# FindMeSAT_MB_1V0.net
KiCad netlist of a schematic drawn in EAGLE
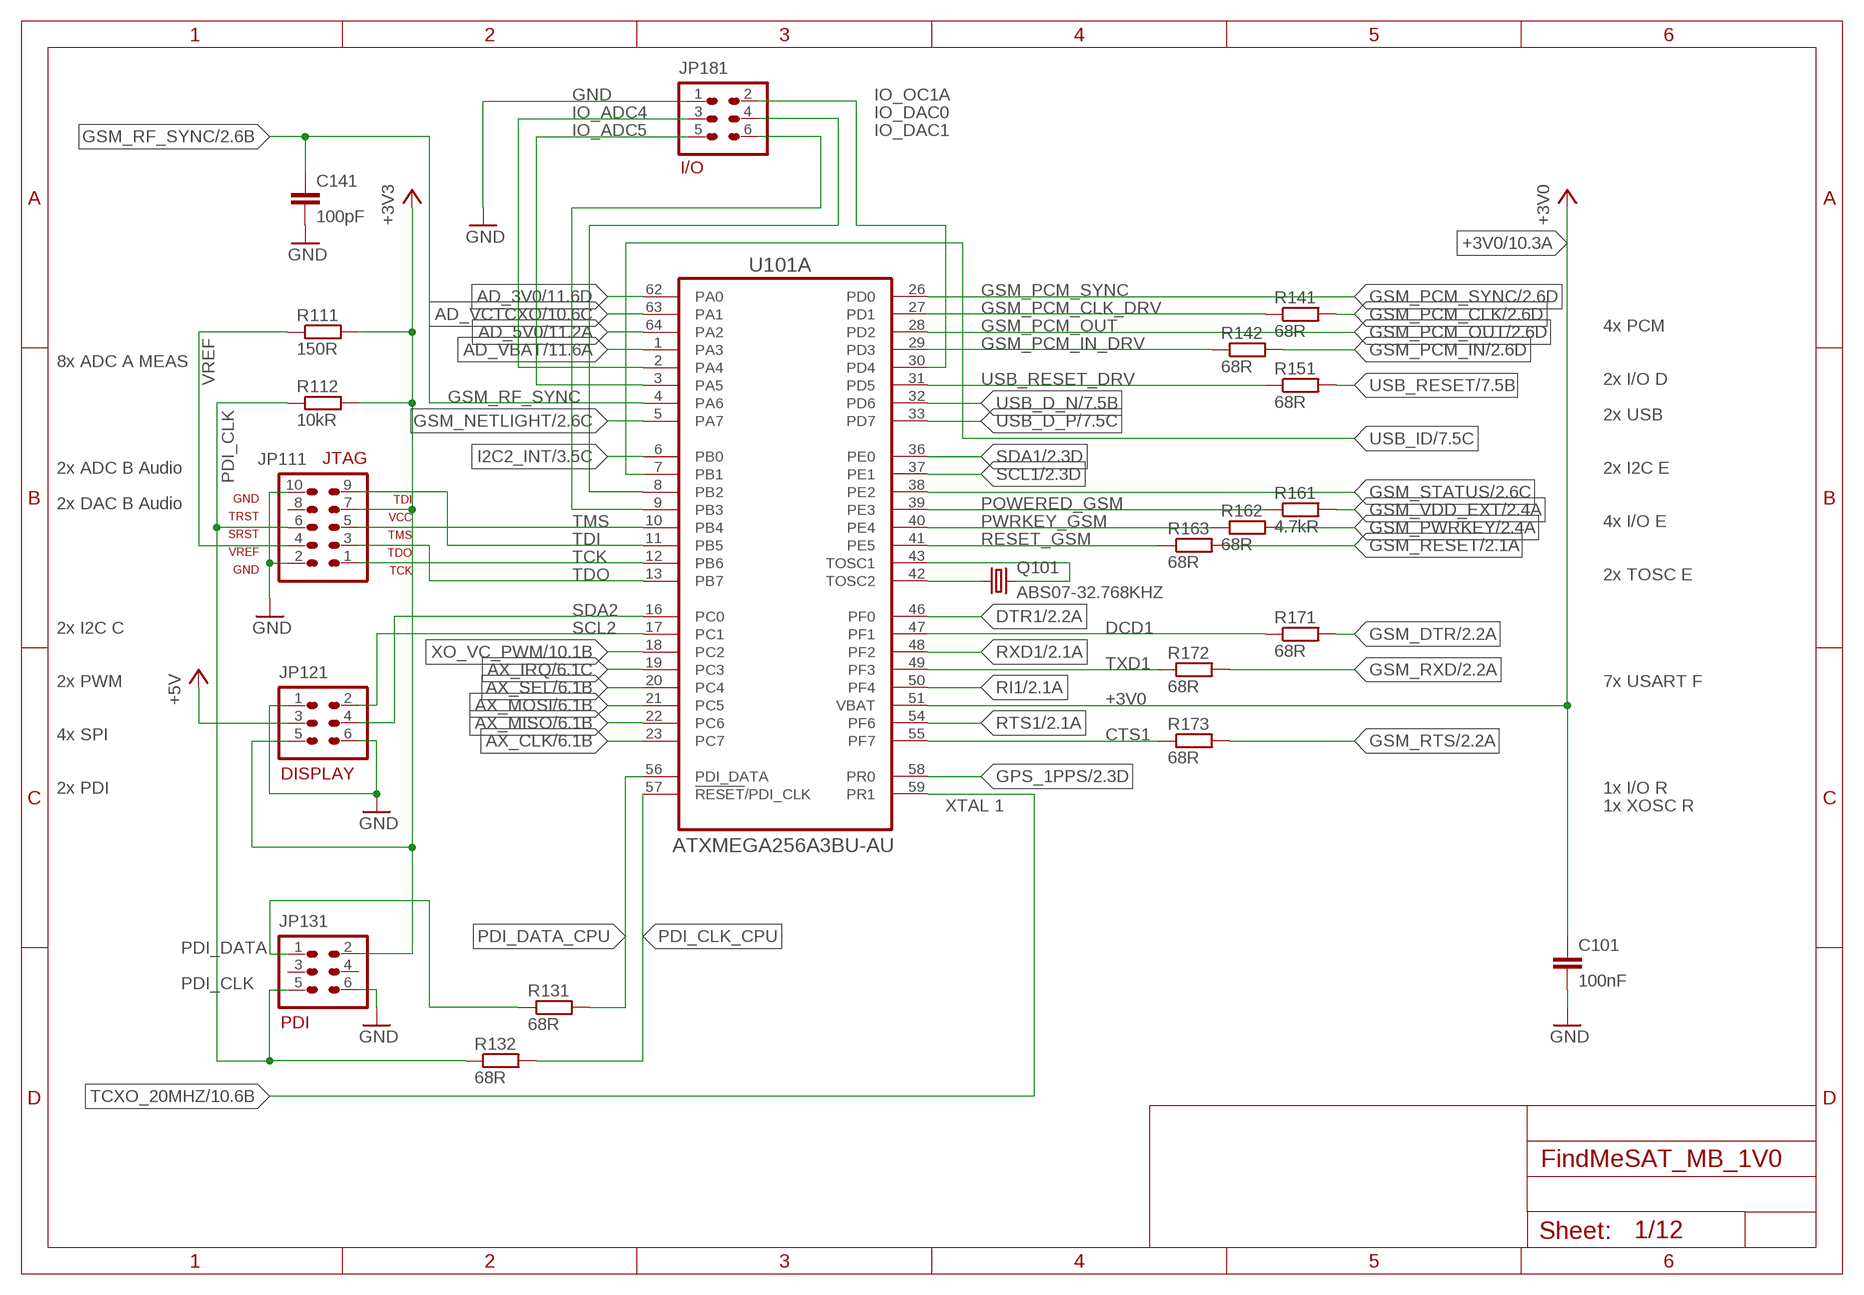
[diagram p0: schematic, sheet 1]
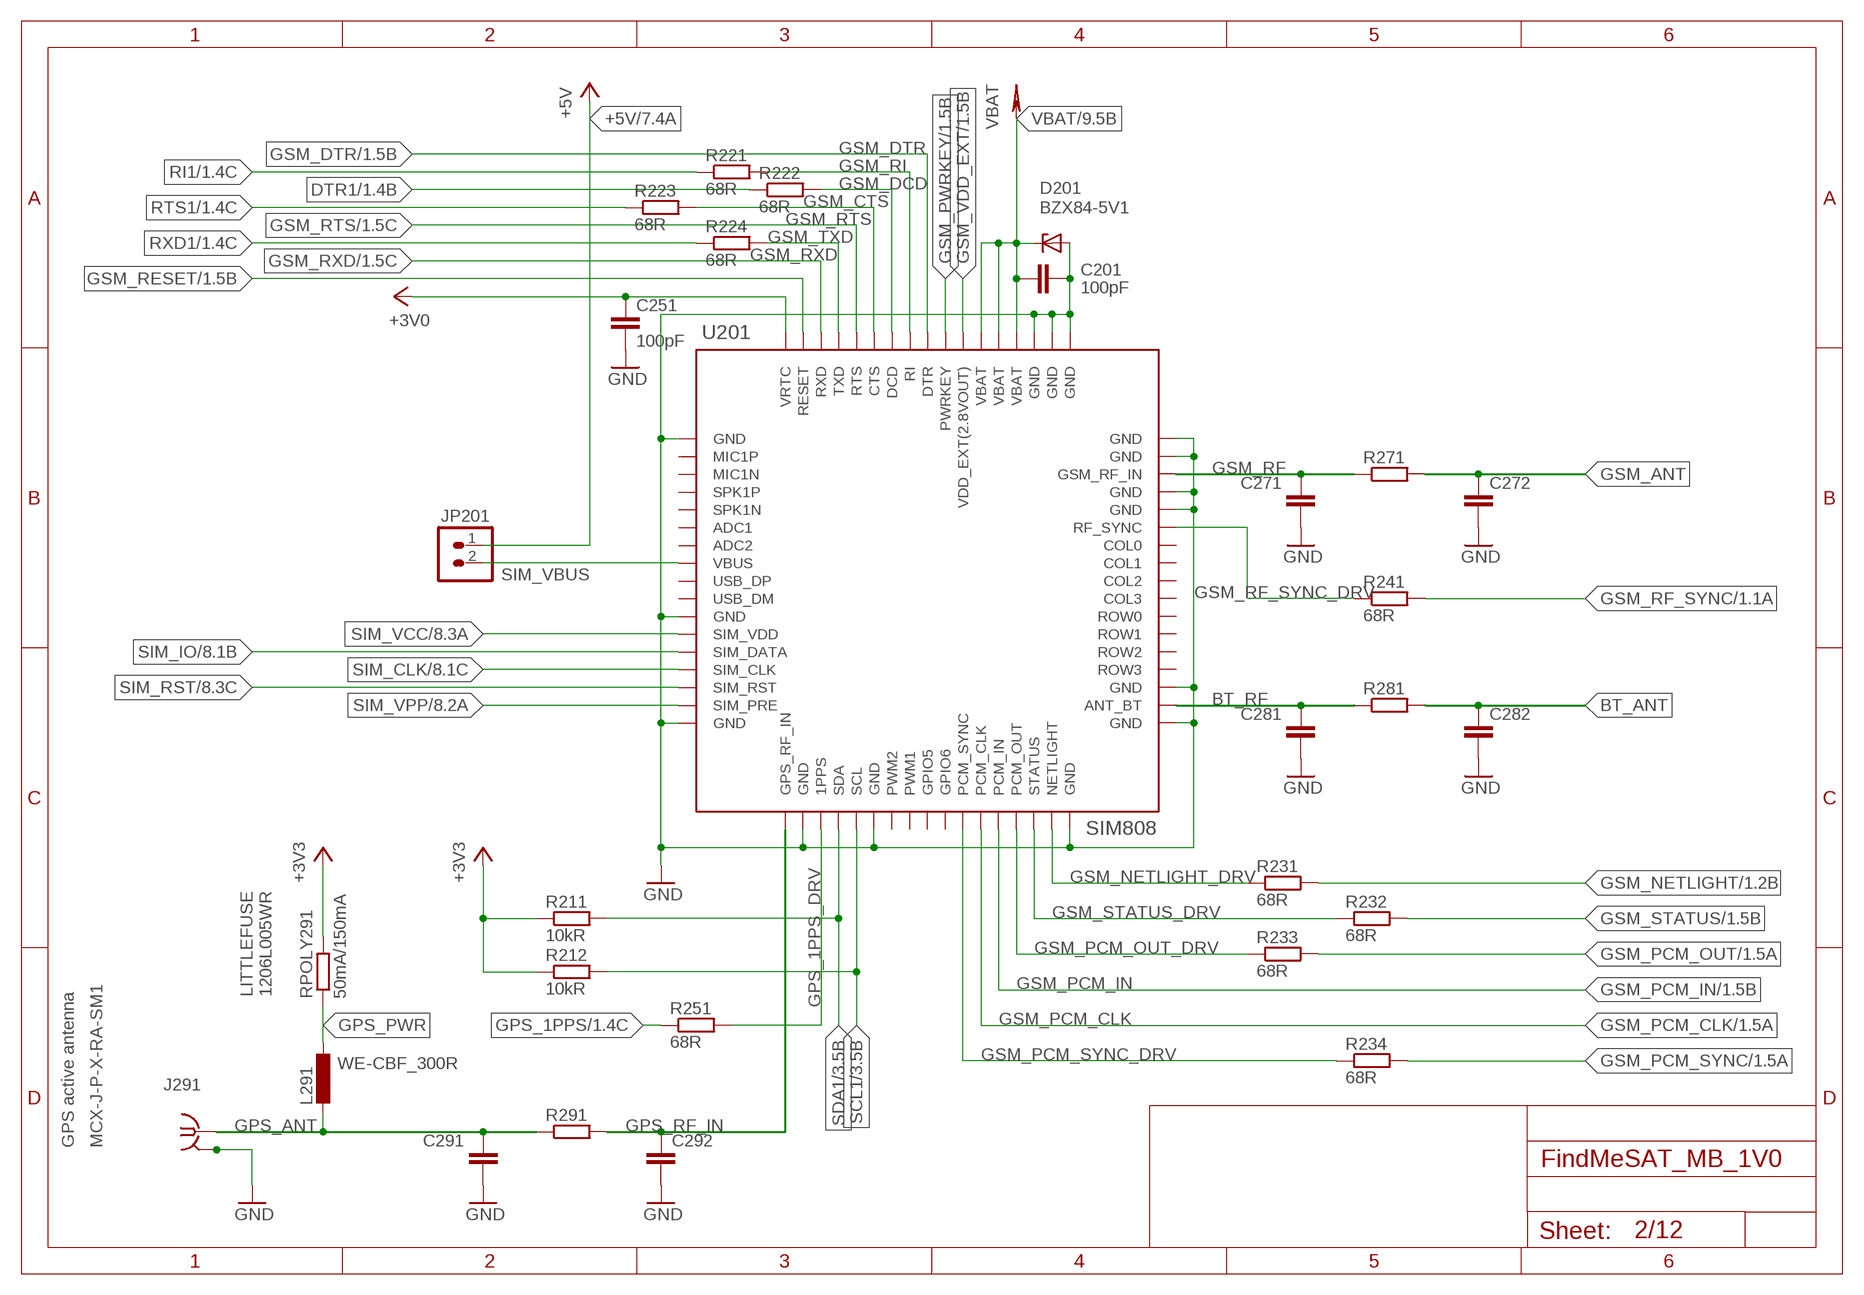
[diagram p1: schematic, sheet 2]
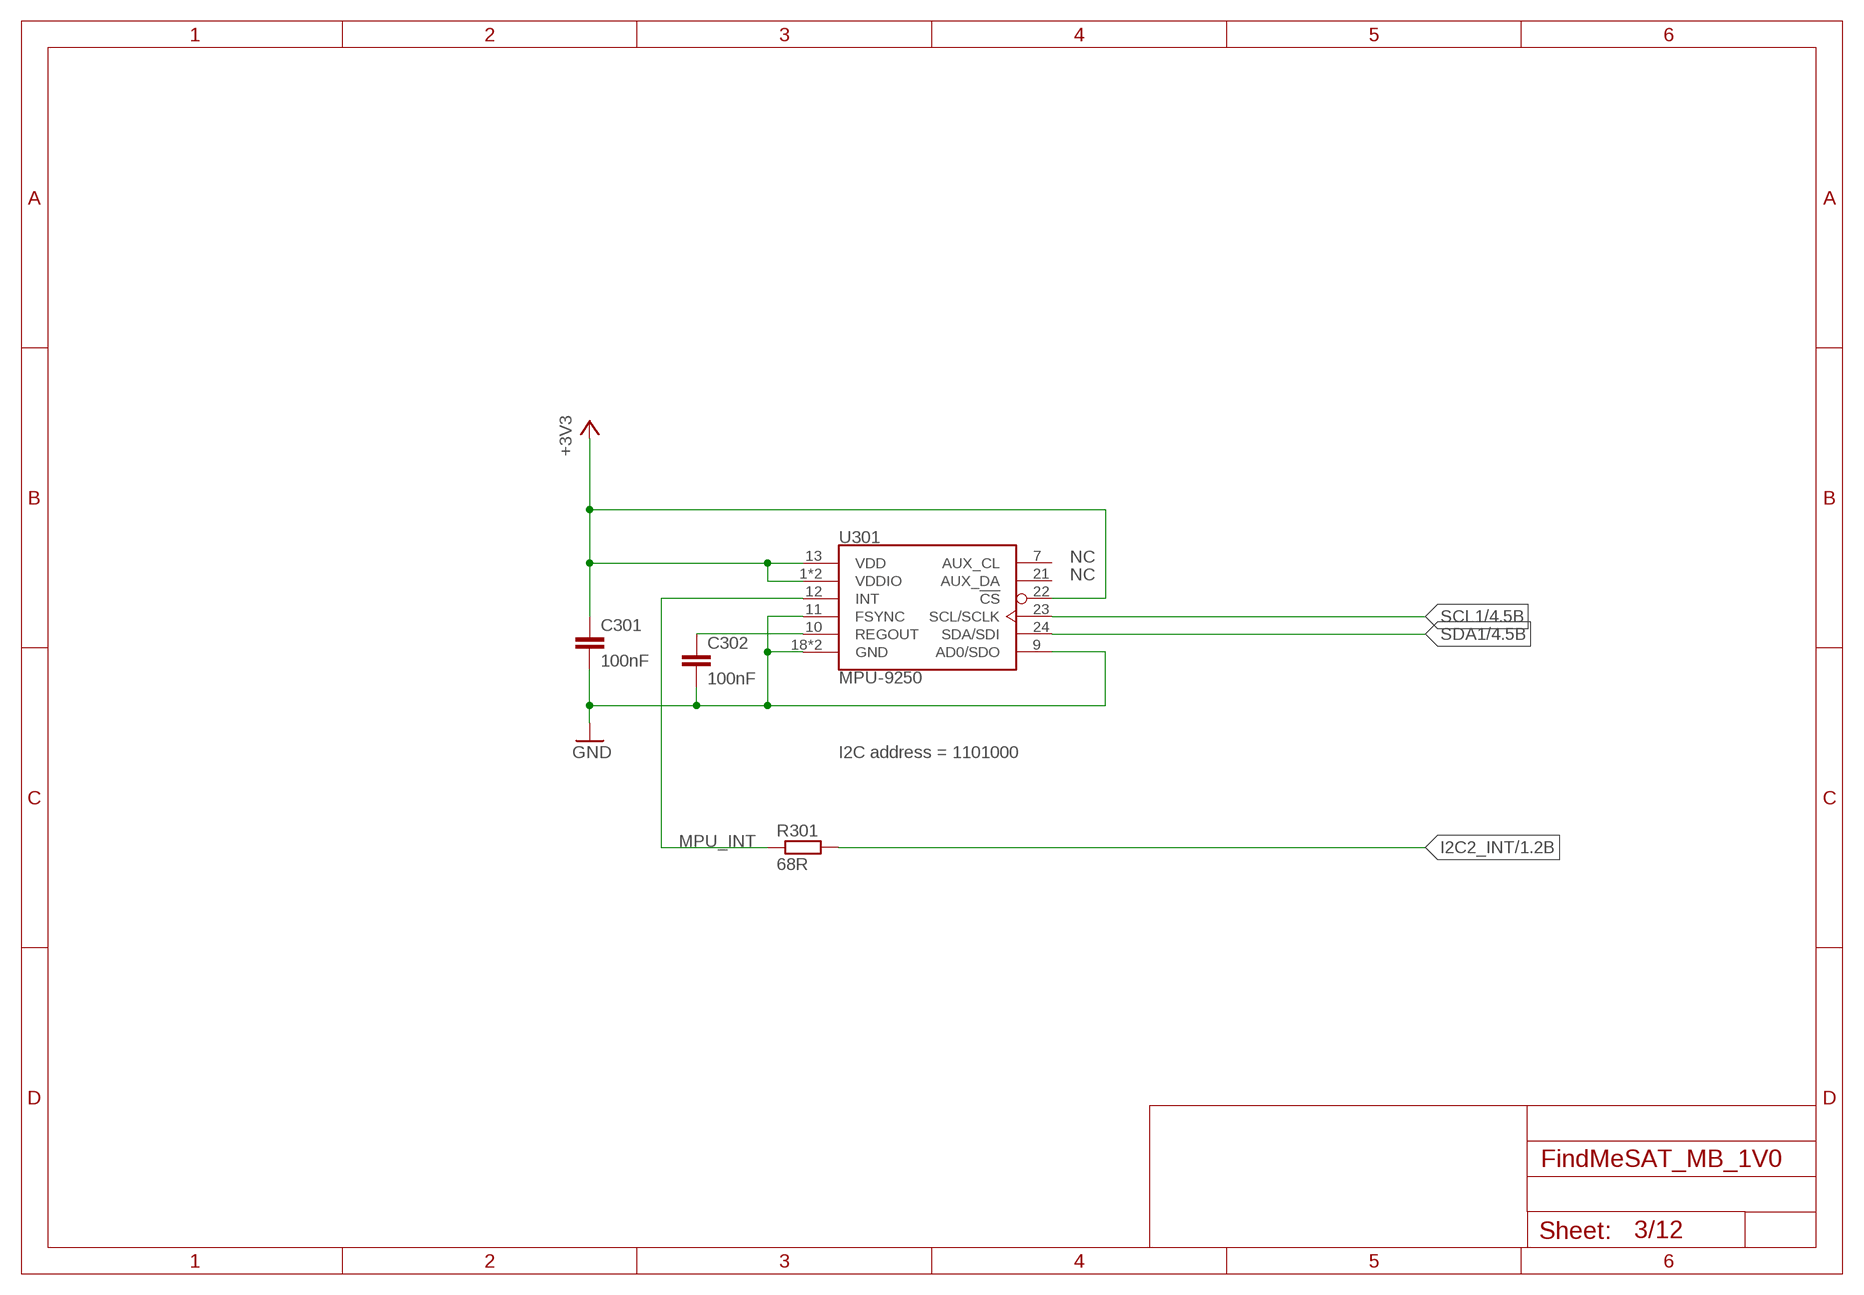
[diagram p2: schematic, sheet 3]
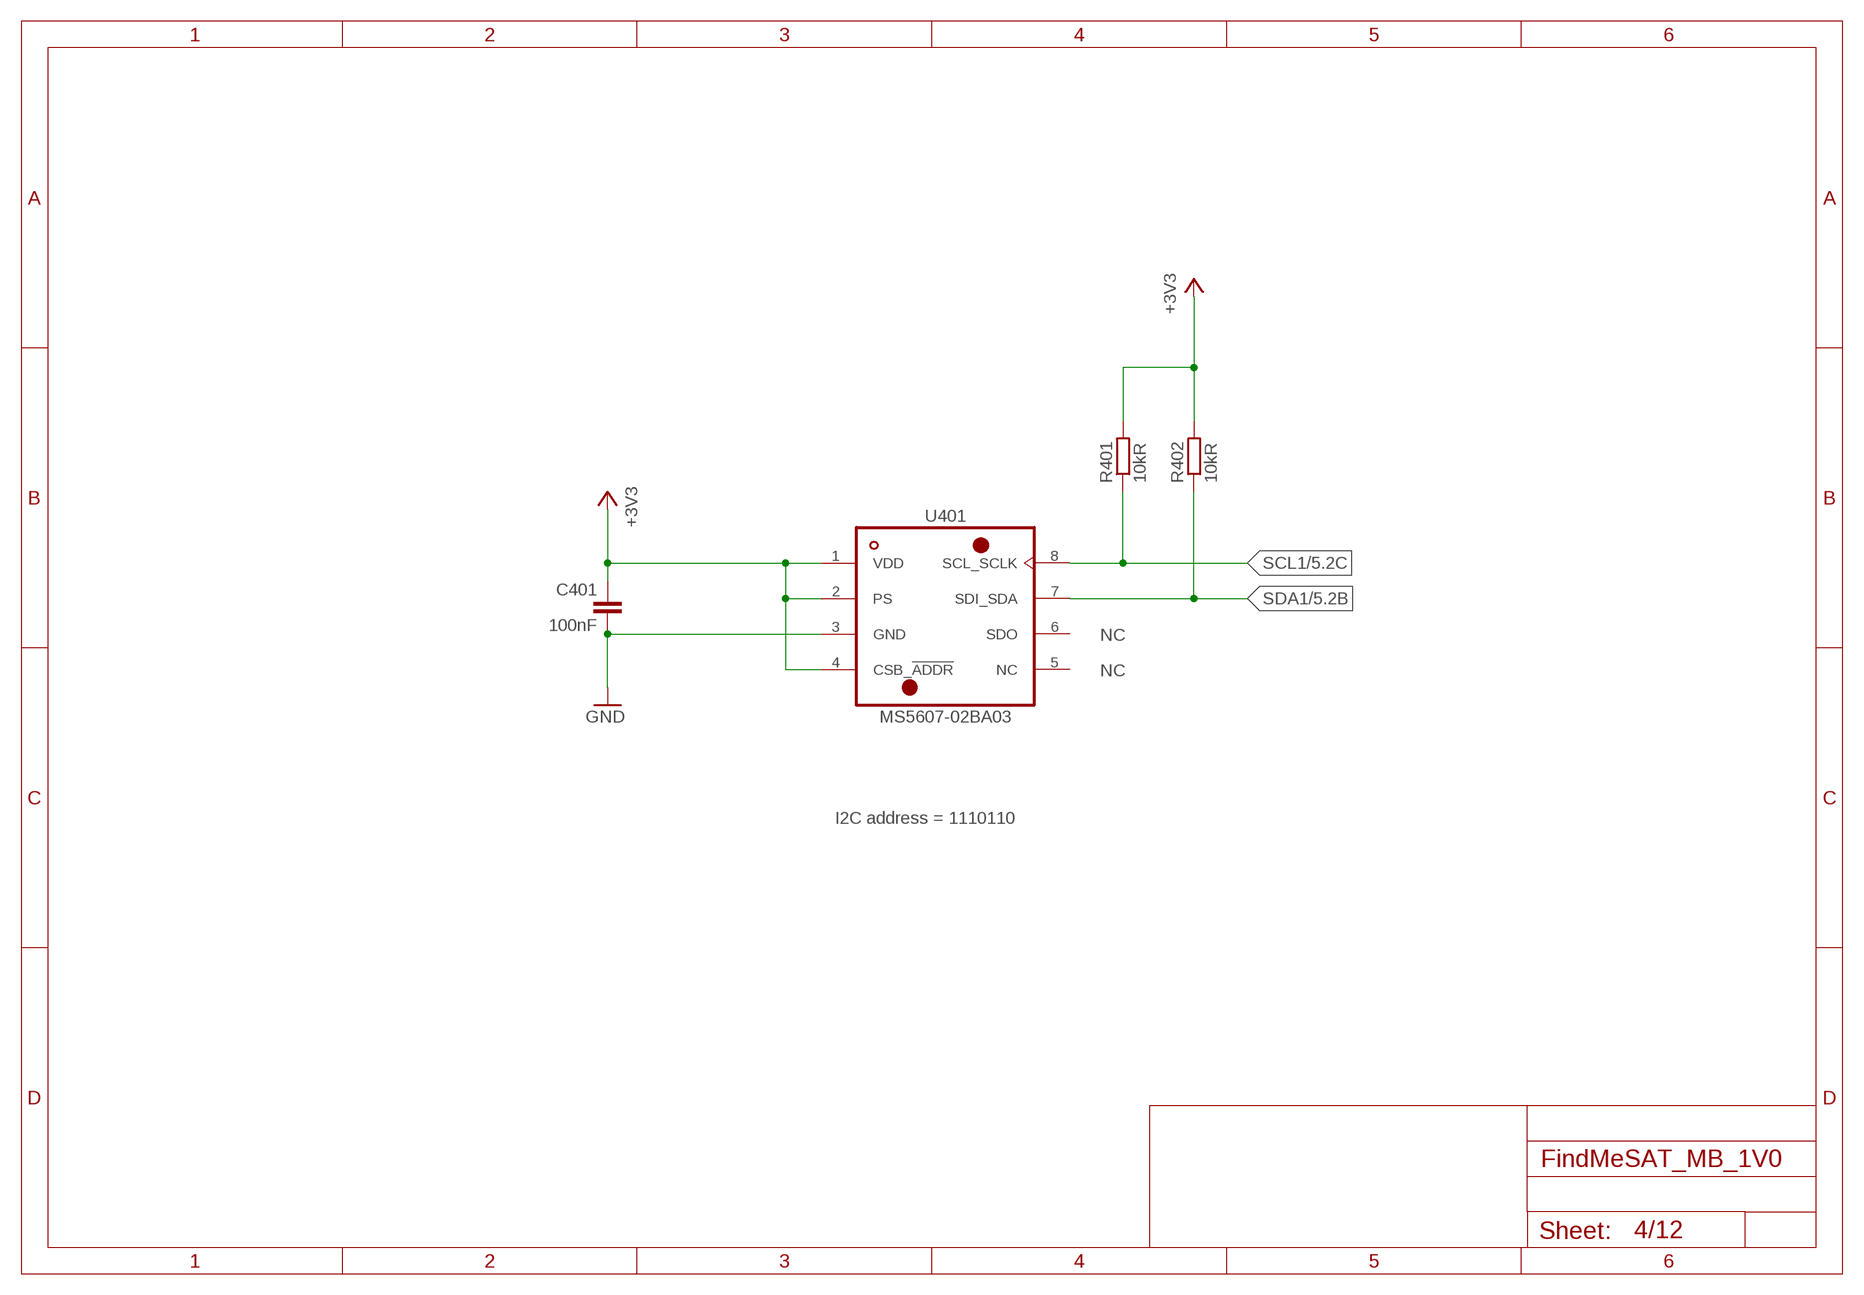
[diagram p3: schematic, sheet 4]
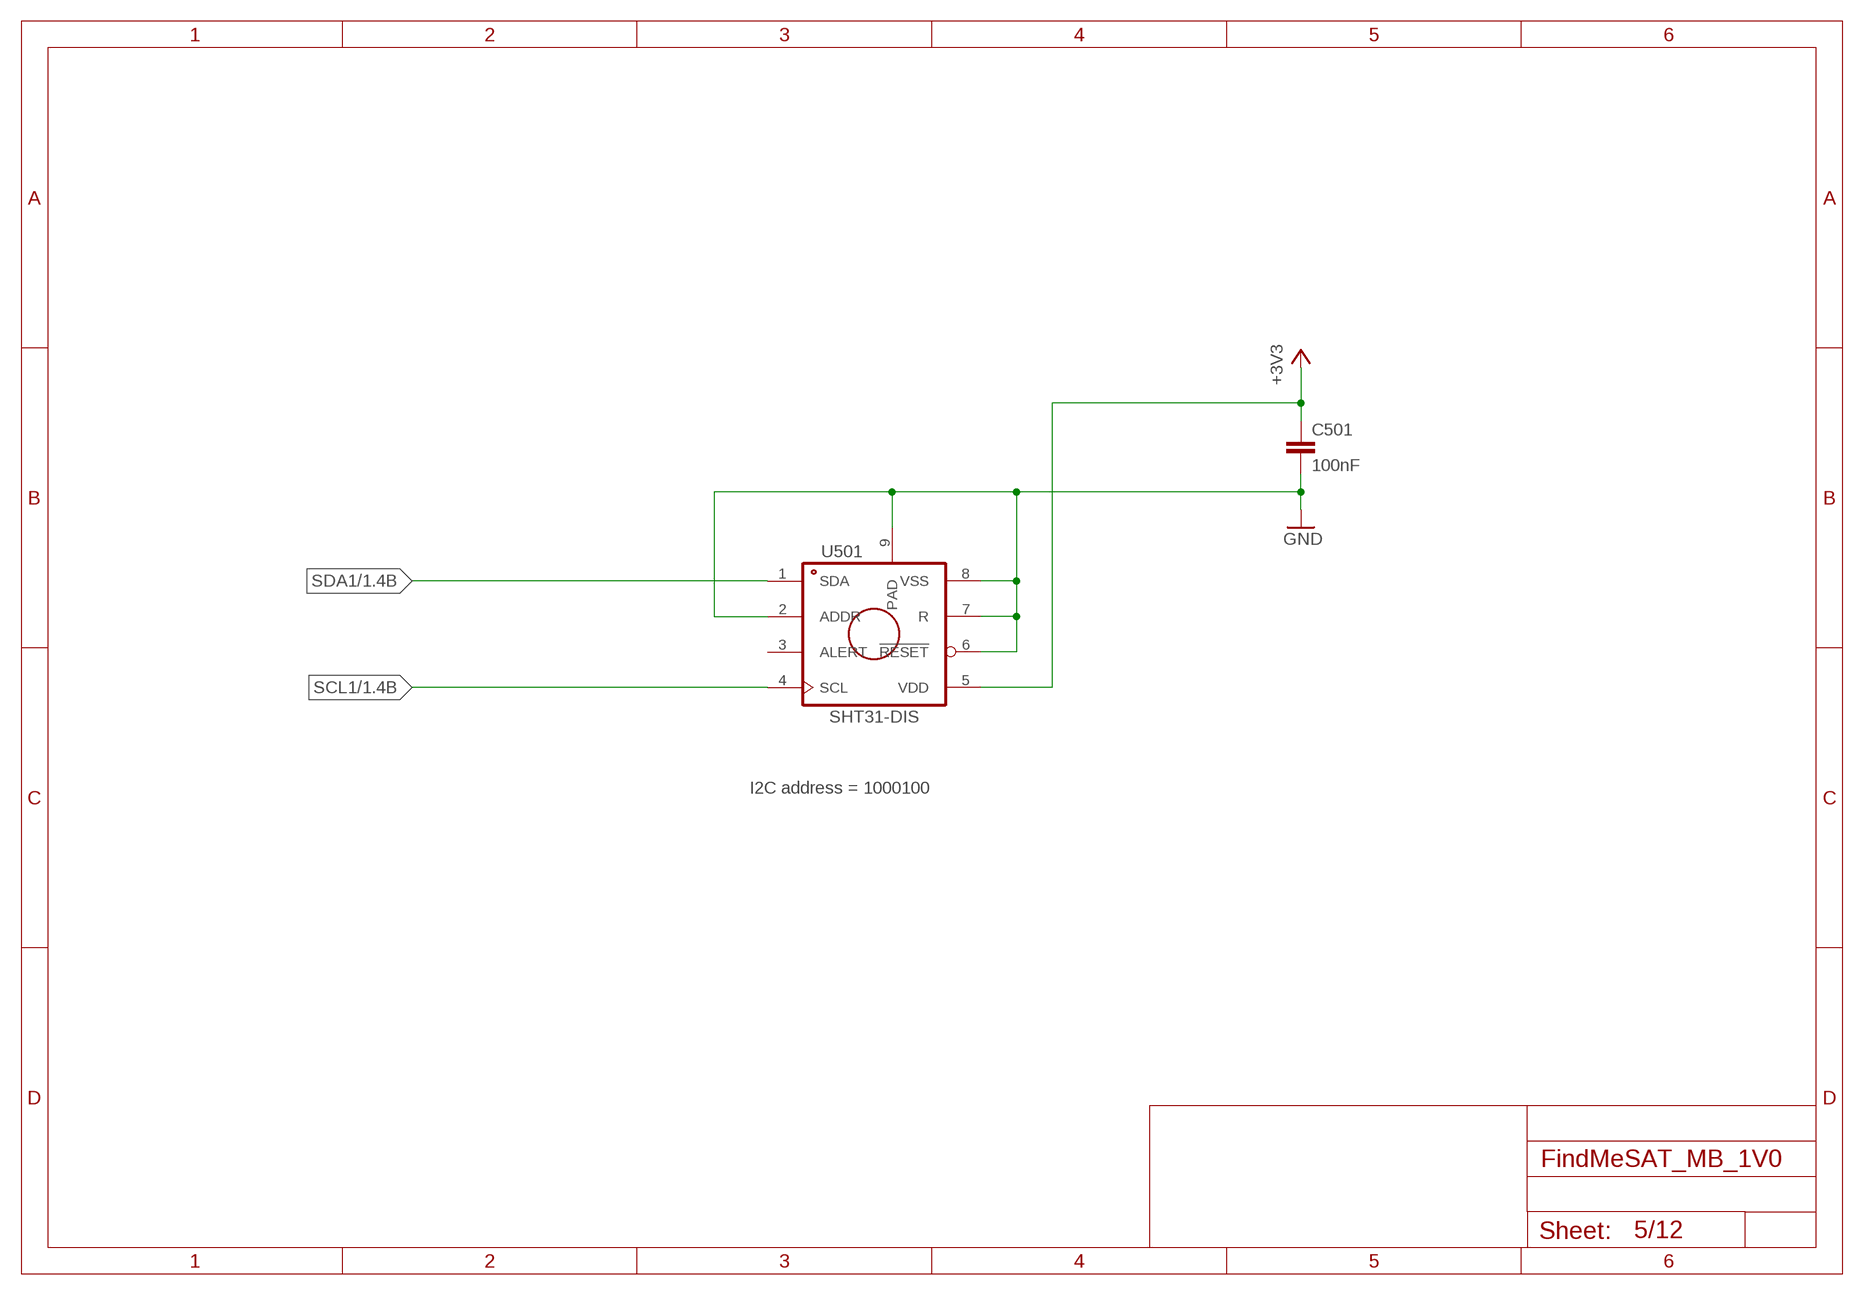
[diagram p4: schematic, sheet 5]
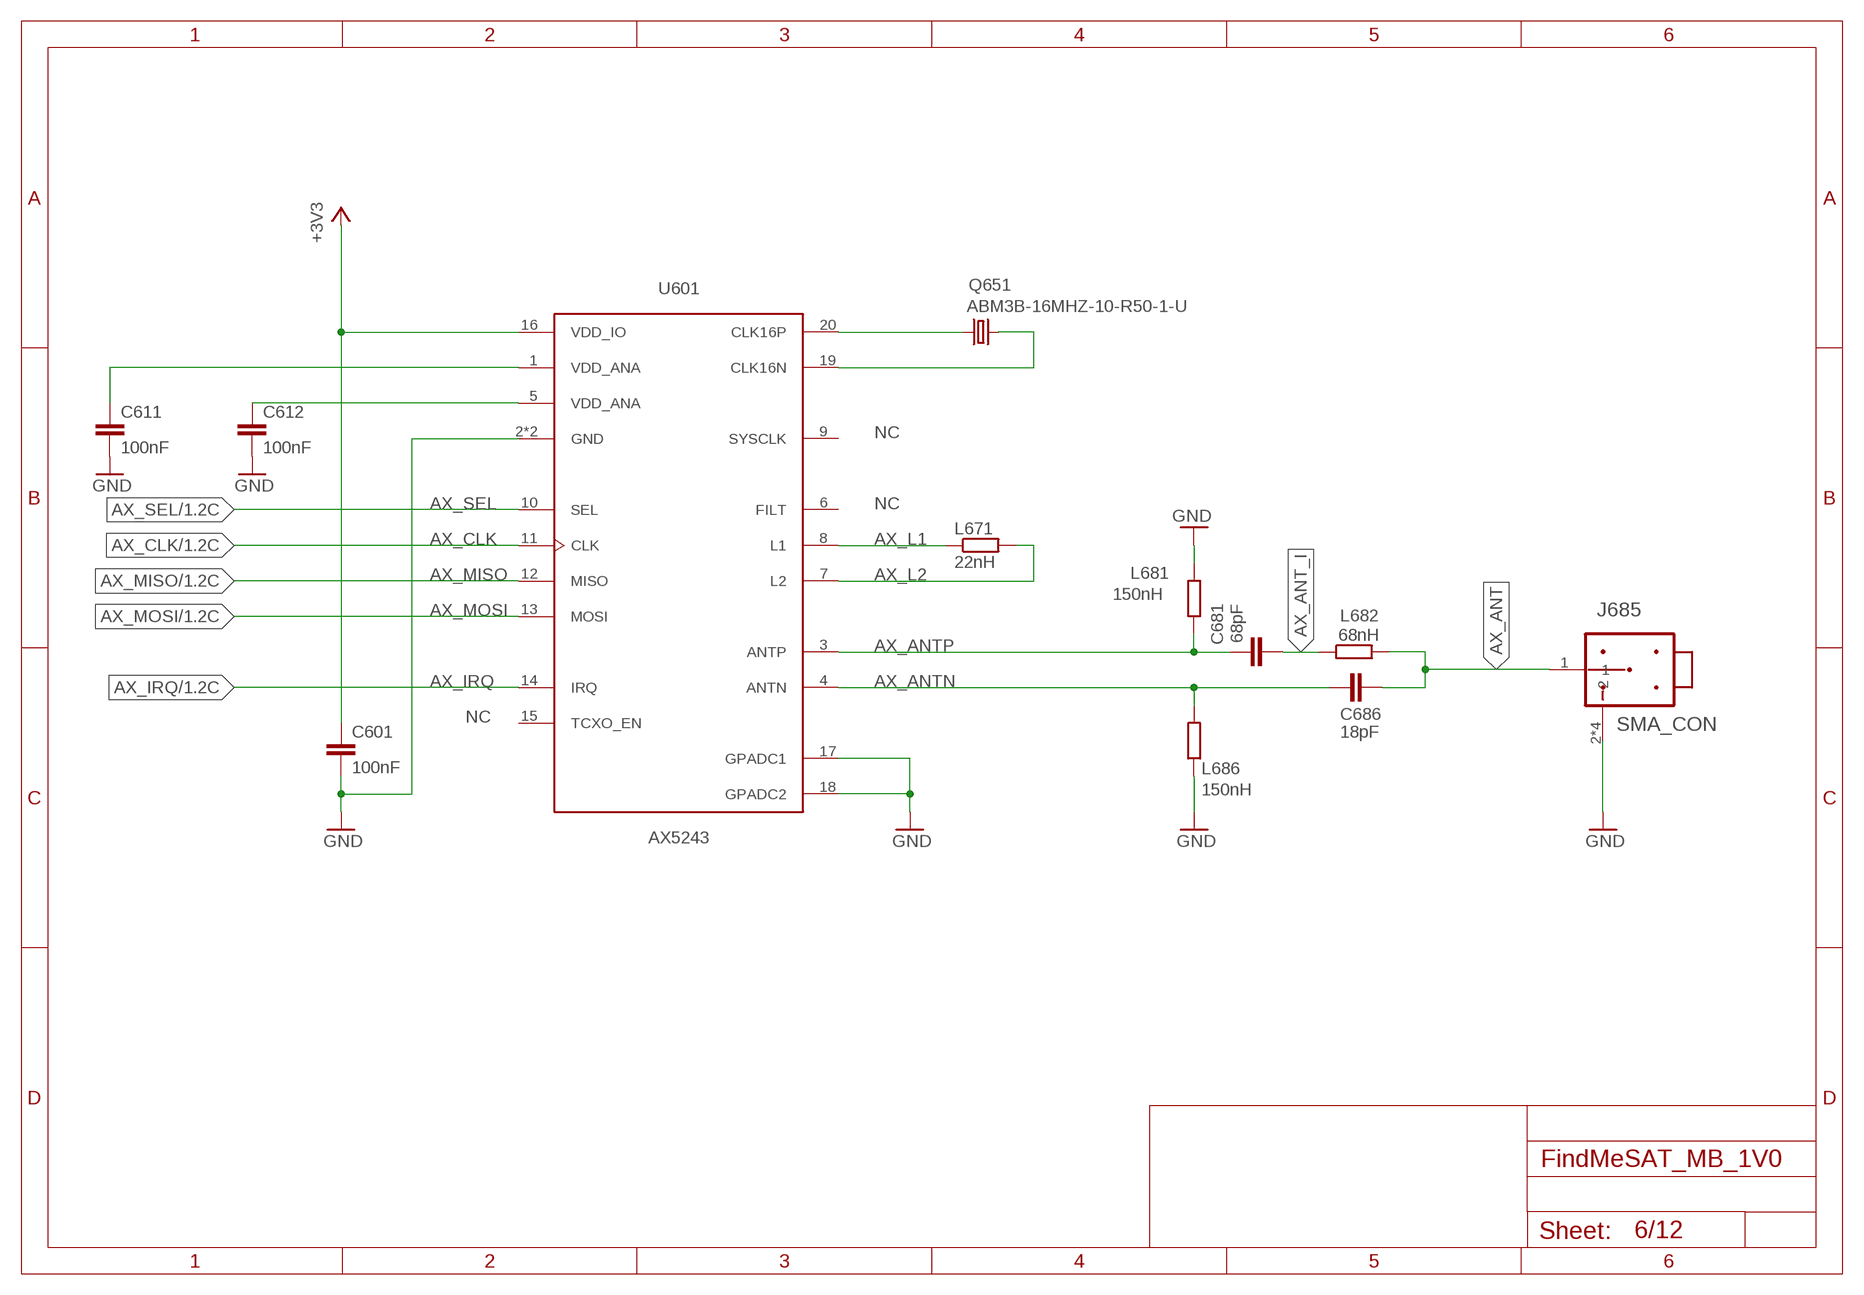
[diagram p5: schematic, sheet 6]
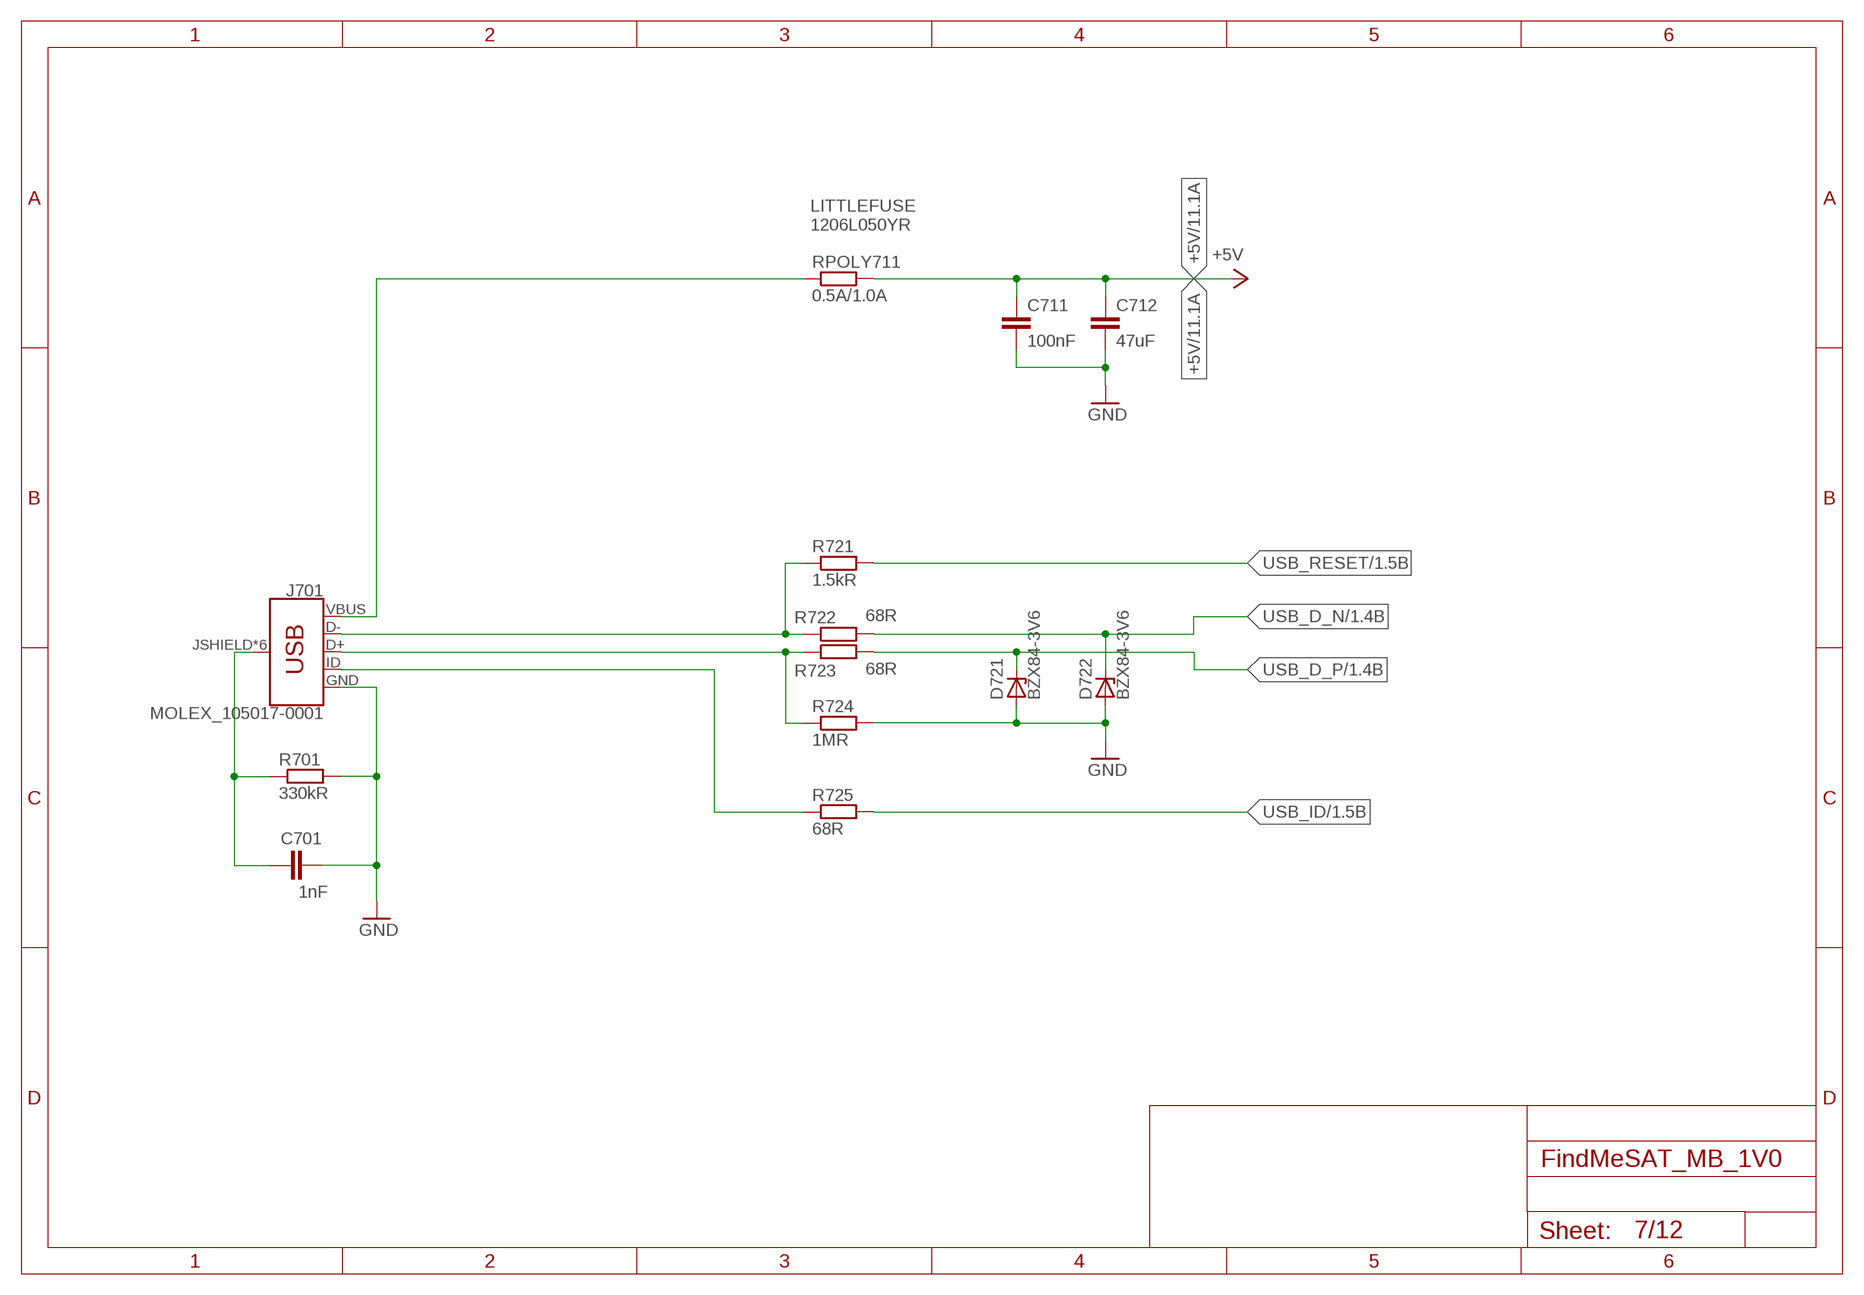
[diagram p6: schematic, sheet 7]
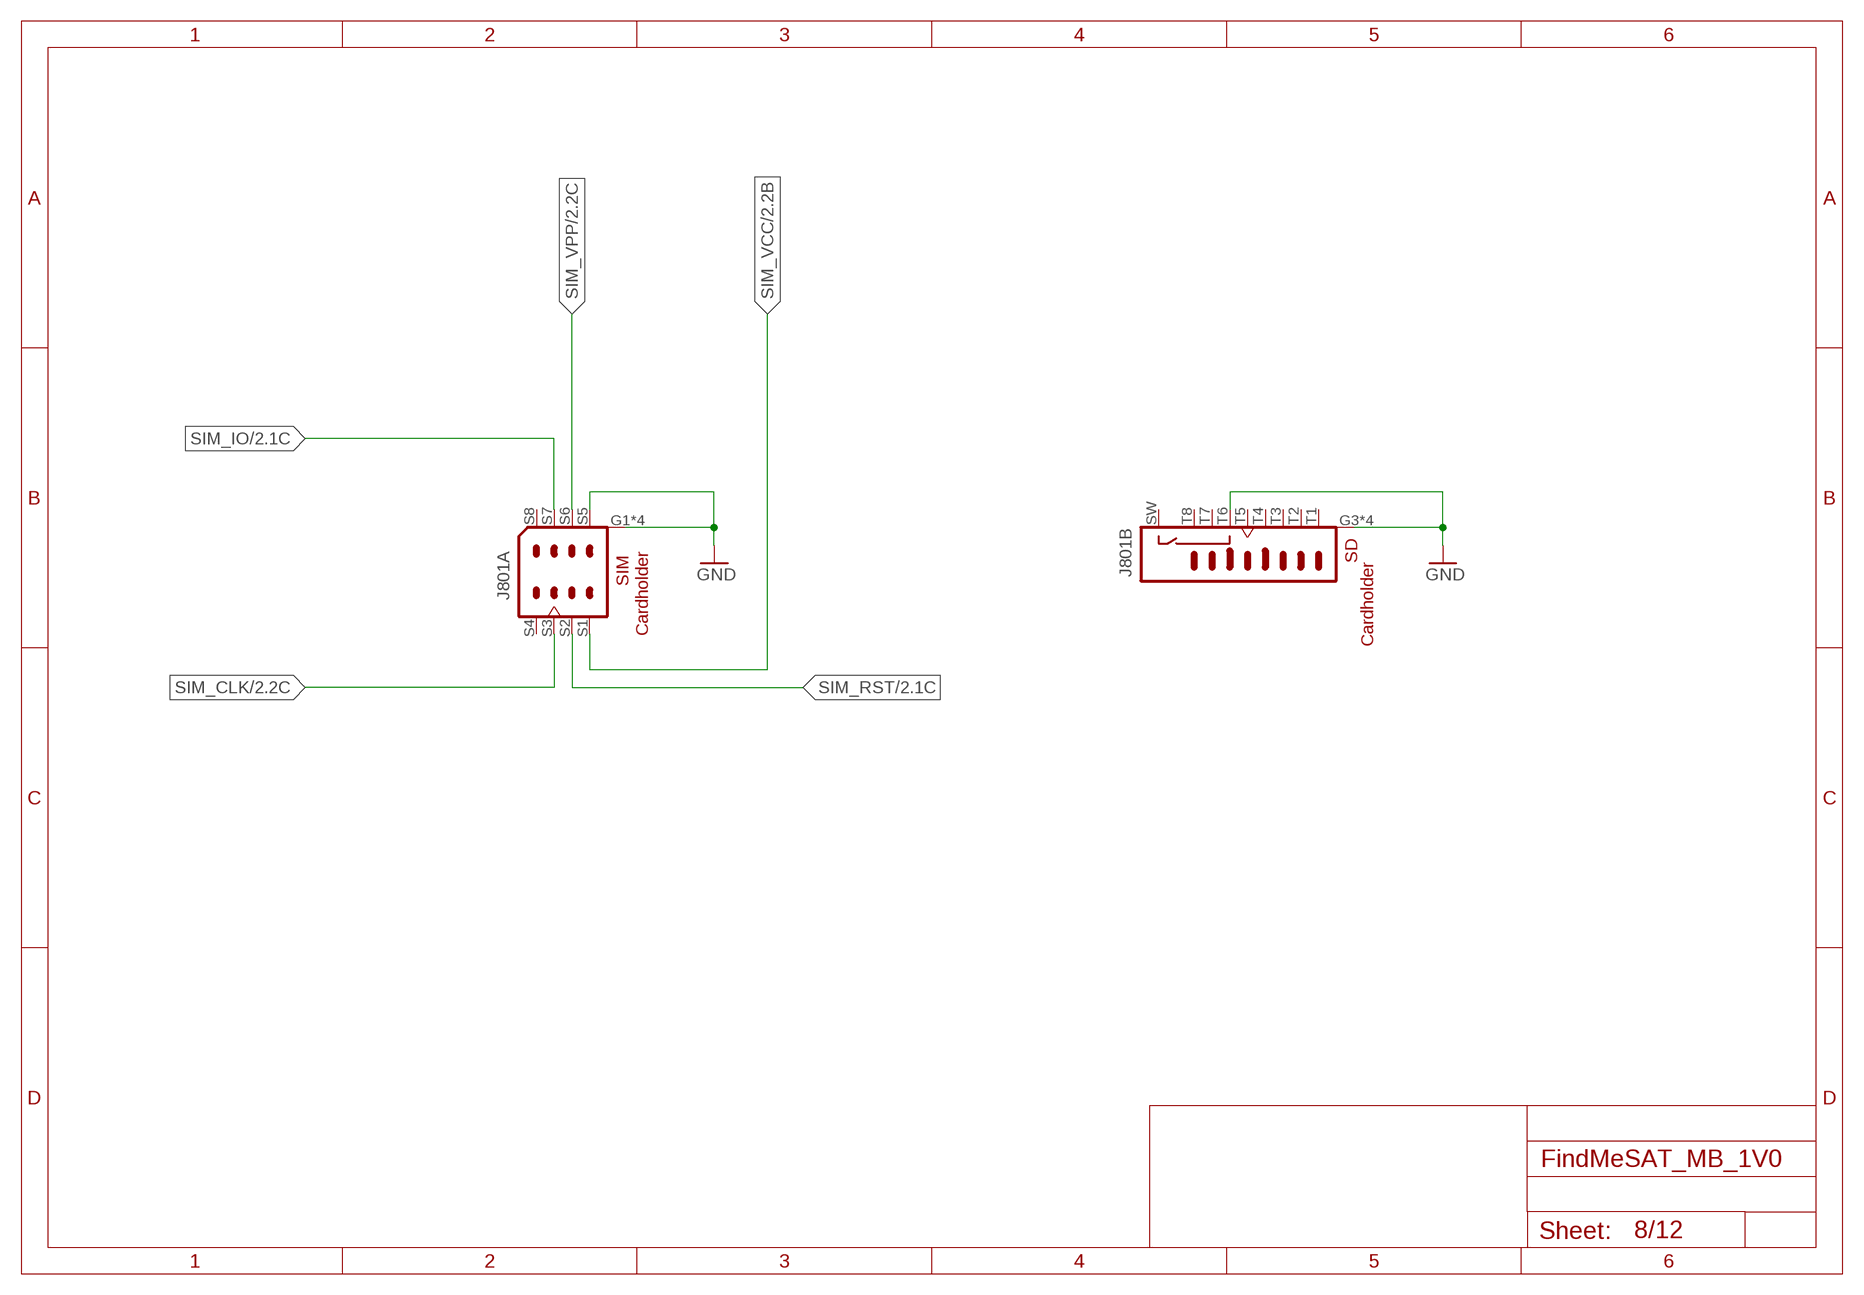
[diagram p7: schematic, sheet 8]
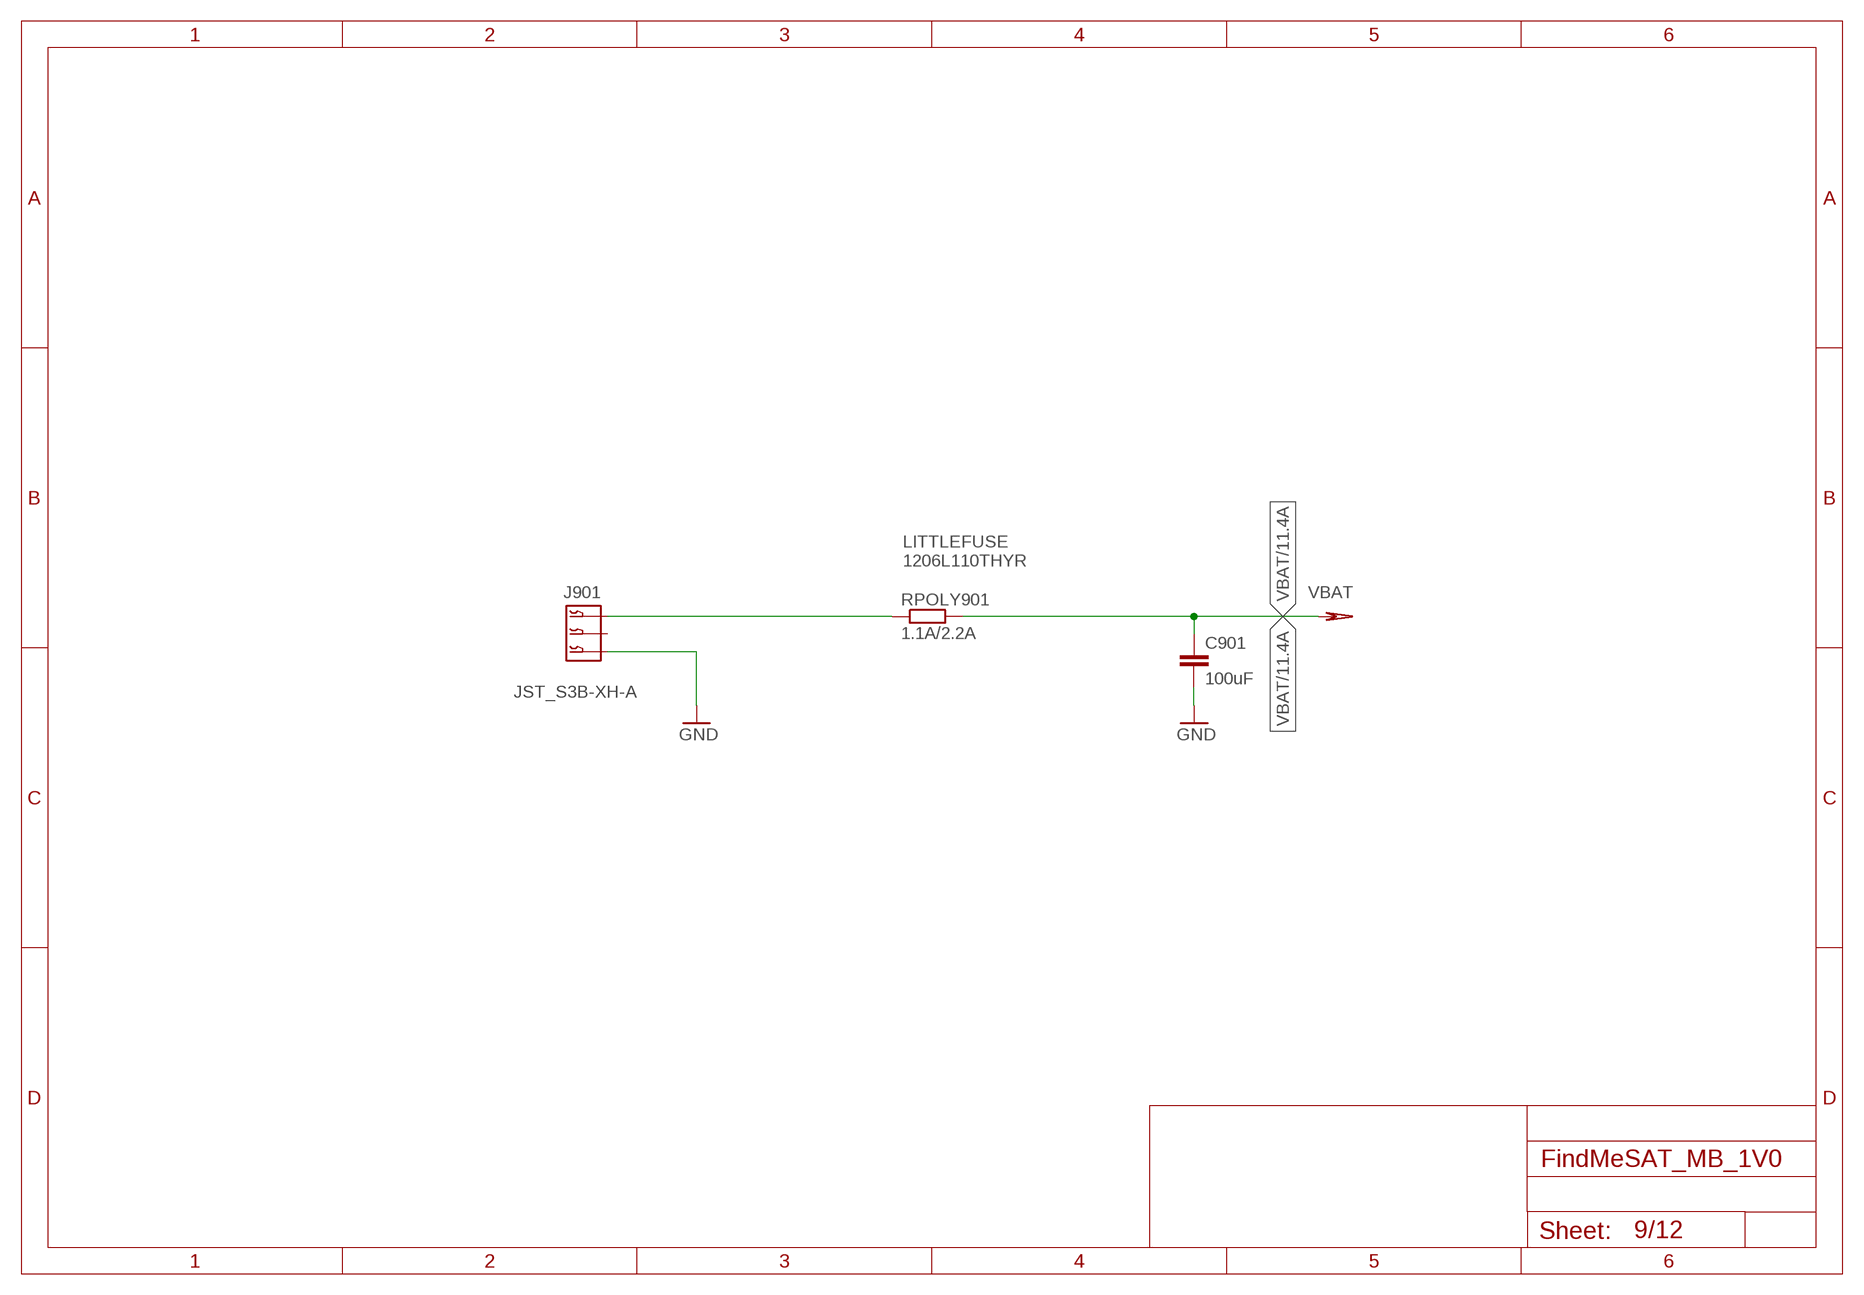
[diagram p8: schematic, sheet 9]
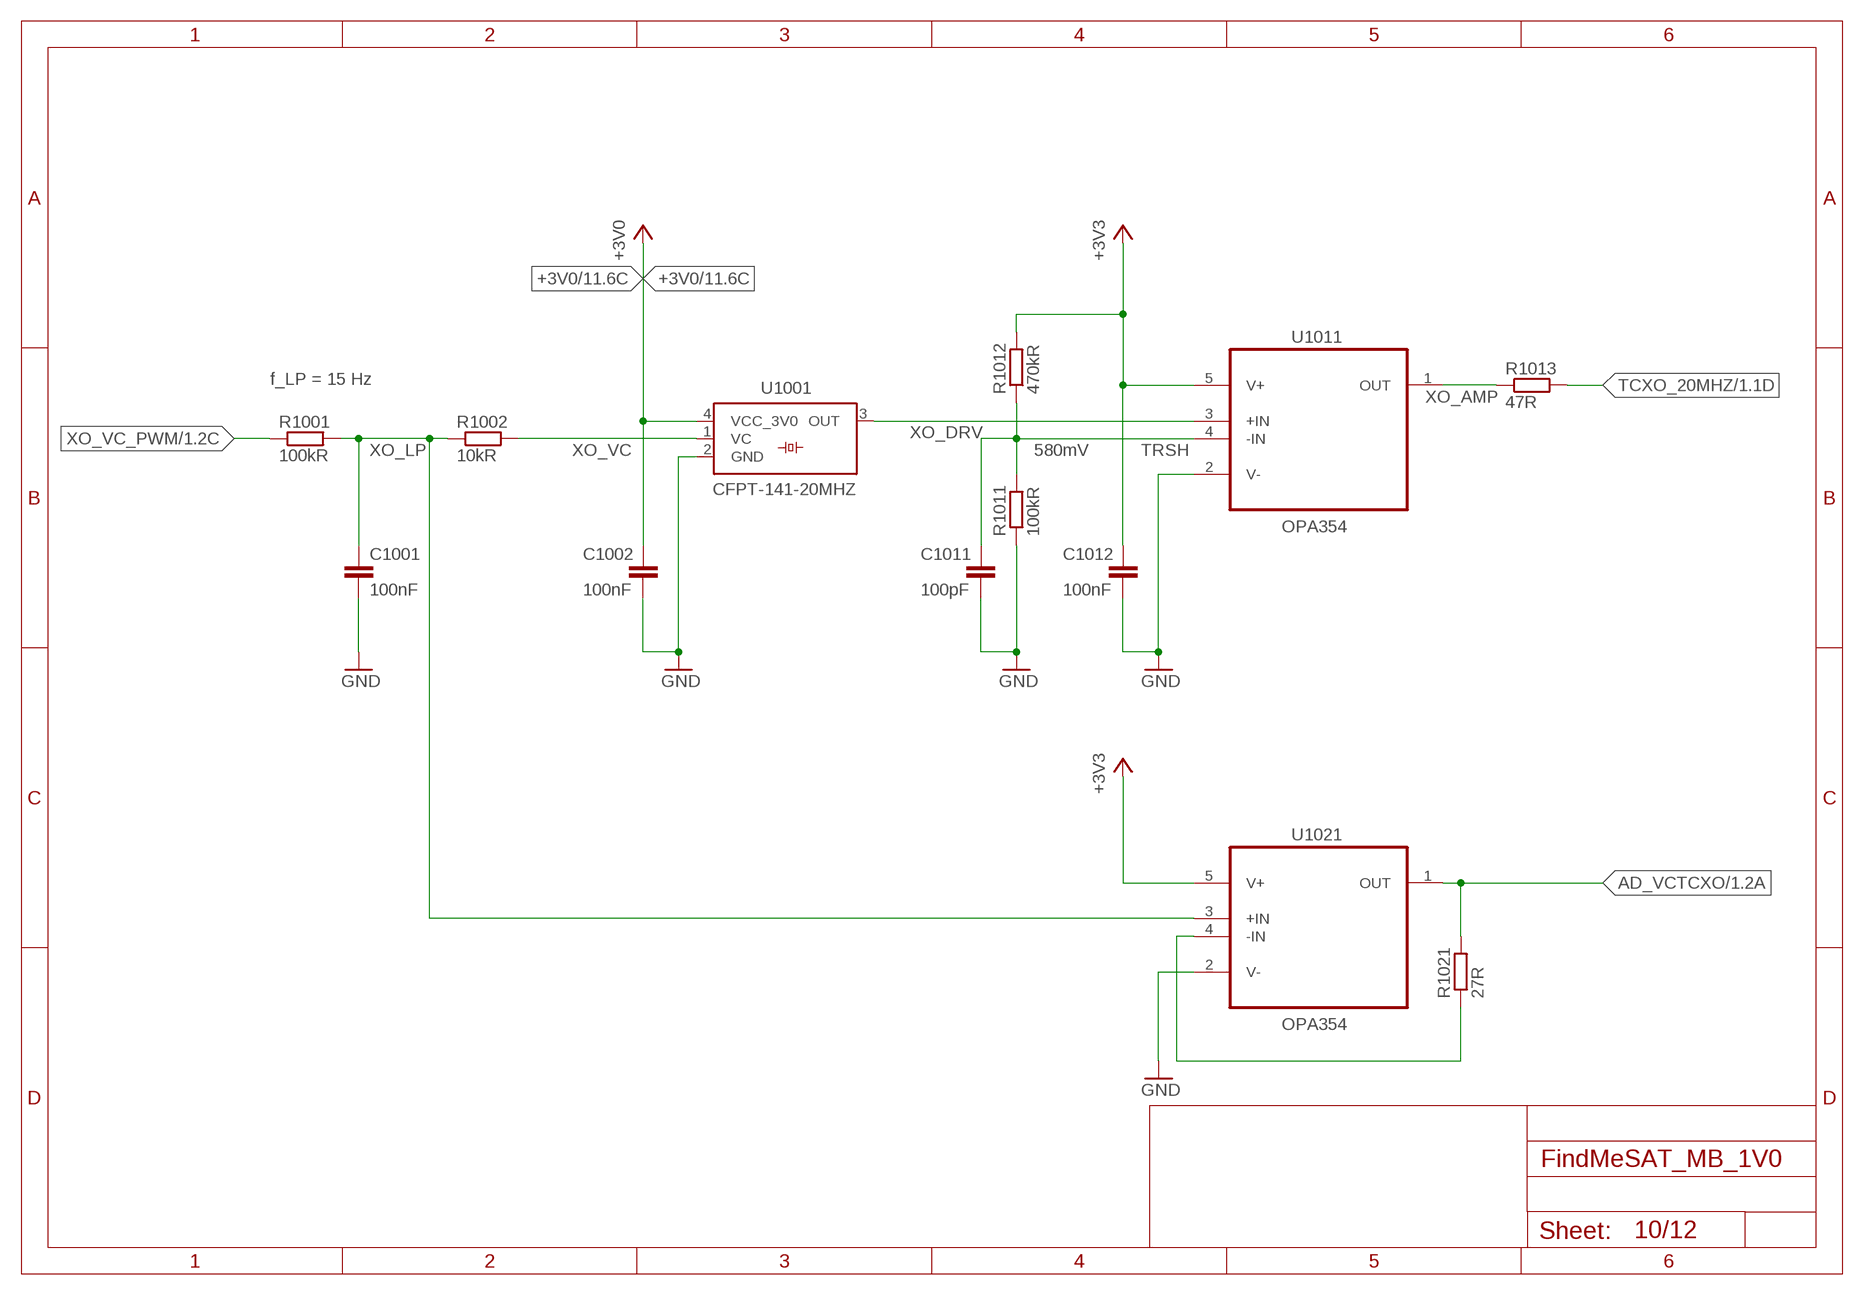
[diagram p9: schematic, sheet 10]
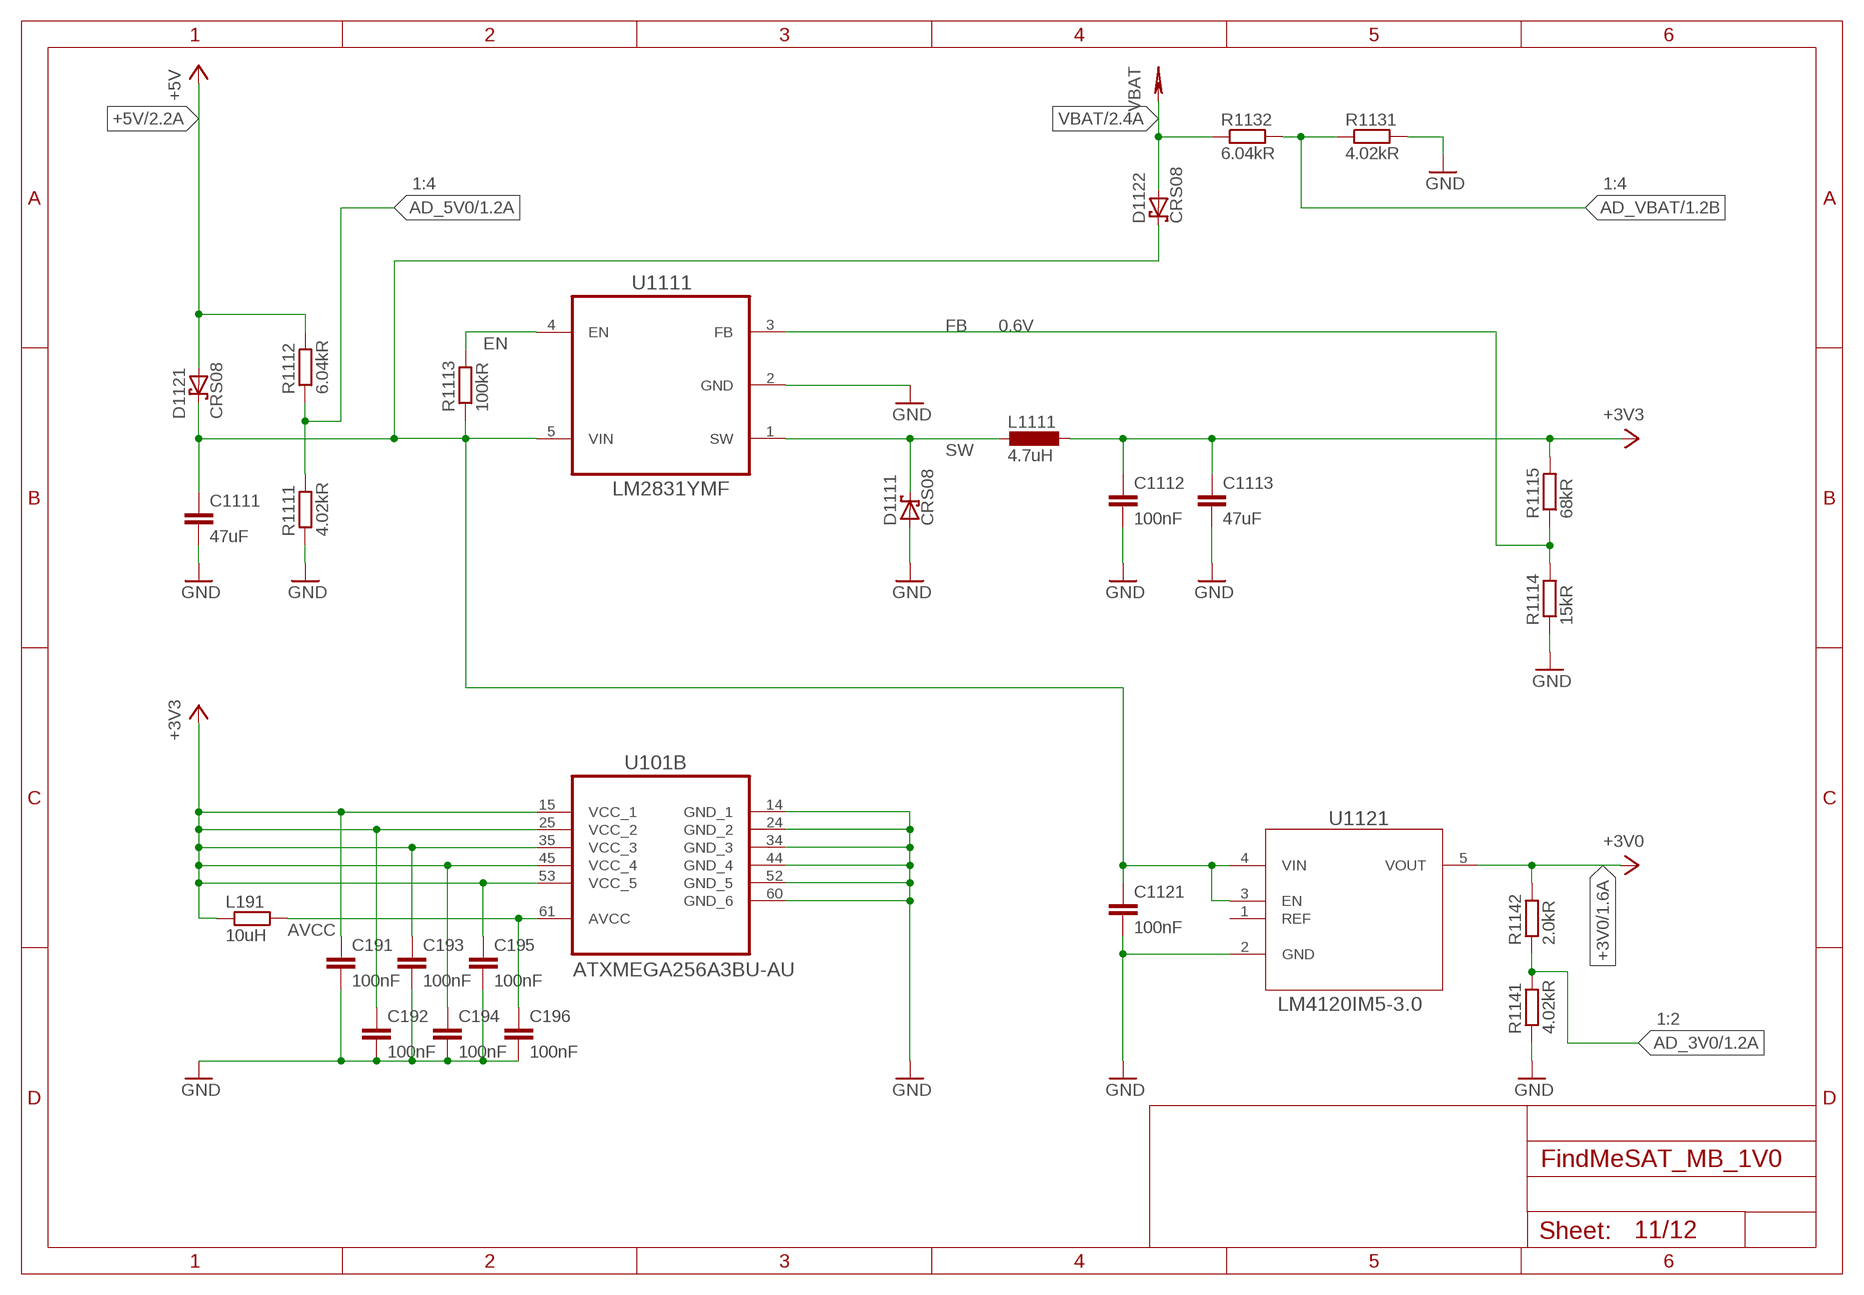
[diagram p10: schematic, sheet 11]
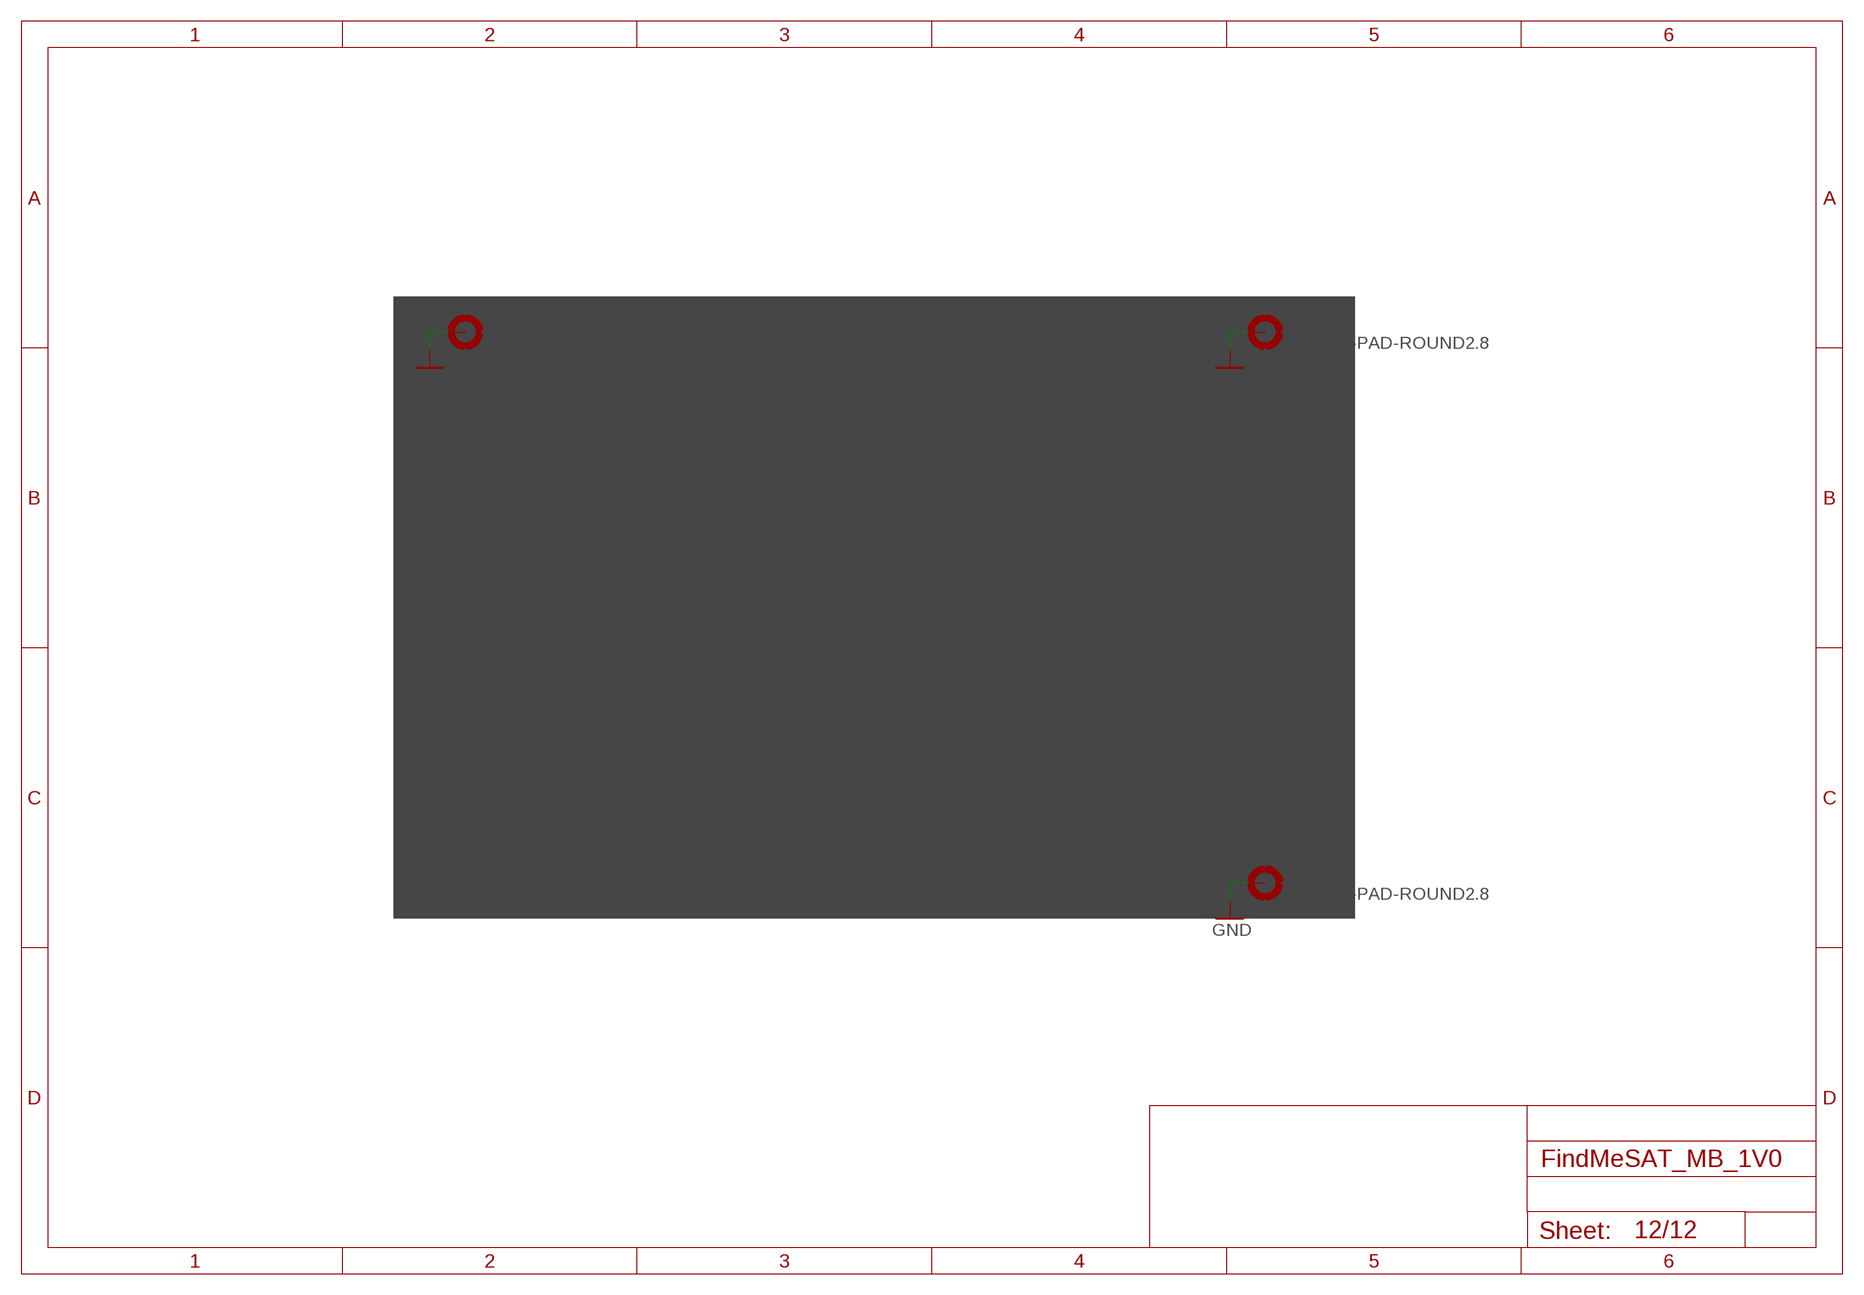
[diagram p11: schematic, sheet 12]

(export (version "E")
  (design (tool "Eeschema 10.0.6"))
  (components
    (comp (ref "C101")
      (value "100nF")
      (footprint "eagle-import:C0603")
      (libsource (lib "eagle-import") (part "C-EUC0603"))
    )
    (comp (ref "C141")
      (value "100pF")
      (footprint "eagle-import:C0603")
      (libsource (lib "eagle-import") (part "C-EUC0603"))
    )
    (comp (ref "JP111")
      (value "AVR-JTAG-10")
      (footprint "eagle-import:AVR-JTAG-10")
      (libsource (lib "eagle-import") (part "AVR-JTAG-10"))
    )
    (comp (ref "JP121")
      (value "HEADER-2X3")
      (footprint "eagle-import:2X03")
      (libsource (lib "eagle-import") (part "HEADER-2X3"))
    )
    (comp (ref "JP131")
      (value "HEADER-2X3")
      (footprint "eagle-import:2X03")
      (libsource (lib "eagle-import") (part "HEADER-2X3"))
    )
    (comp (ref "JP181")
      (value "HEADER-2X3")
      (footprint "eagle-import:2X03")
      (libsource (lib "eagle-import") (part "HEADER-2X3"))
    )
    (comp (ref "Q101")
      (value "ABS07-32.768KHZ")
      (footprint "eagle-import:ABS07")
      (fields (field (name "MANUFACTURER") "ABS07-32.768KHZ-1-T"))
      (libsource (lib "eagle-import") (part "ABS07-32.768KHZ"))
    )
    (comp (ref "R111")
      (value "150R")
      (footprint "eagle-import:R0805")
      (libsource (lib "eagle-import") (part "R-EU_R0805"))
    )
    (comp (ref "R112")
      (value "10kR")
      (footprint "eagle-import:R0603")
      (libsource (lib "eagle-import") (part "R-EU_R0603"))
    )
    (comp (ref "R131")
      (value "68R")
      (footprint "eagle-import:R0603")
      (libsource (lib "eagle-import") (part "R-EU_R0603"))
    )
    (comp (ref "R132")
      (value "68R")
      (footprint "eagle-import:R0603")
      (libsource (lib "eagle-import") (part "R-EU_R0603"))
    )
    (comp (ref "R141")
      (value "68R")
      (footprint "eagle-import:R0603")
      (libsource (lib "eagle-import") (part "R-EU_R0603"))
    )
    (comp (ref "R142")
      (value "68R")
      (footprint "eagle-import:R0603")
      (libsource (lib "eagle-import") (part "R-EU_R0603"))
    )
    (comp (ref "R151")
      (value "68R")
      (footprint "eagle-import:R0603")
      (libsource (lib "eagle-import") (part "R-EU_R0603"))
    )
    (comp (ref "R161")
      (value "4.7kR")
      (footprint "eagle-import:R0603")
      (libsource (lib "eagle-import") (part "R-EU_R0603"))
    )
    (comp (ref "R162")
      (value "68R")
      (footprint "eagle-import:R0603")
      (libsource (lib "eagle-import") (part "R-EU_R0603"))
    )
    (comp (ref "R163")
      (value "68R")
      (footprint "eagle-import:R0603")
      (libsource (lib "eagle-import") (part "R-EU_R0603"))
    )
    (comp (ref "R171")
      (value "68R")
      (footprint "eagle-import:R0603")
      (libsource (lib "eagle-import") (part "R-EU_R0603"))
    )
    (comp (ref "R172")
      (value "68R")
      (footprint "eagle-import:R0603")
      (libsource (lib "eagle-import") (part "R-EU_R0603"))
    )
    (comp (ref "R173")
      (value "68R")
      (footprint "eagle-import:R0603")
      (libsource (lib "eagle-import") (part "R-EU_R0603"))
    )
    (comp (ref "U101")
      (value "ATXMEGA256A3BU-AU")
      (footprint "eagle-import:QFP80P1600X1600X120-64N")
      (libsource (lib "eagle-import") (part "ATXMEGA256A3BU-AU"))
    )
    (comp (ref "H1201")
      (value "MOUNT-PAD-ROUND2.8")
      (footprint "eagle-import:2,8-PAD")
      (libsource (lib "eagle-import") (part "MOUNT-PAD-ROUND2.8"))
    )
    (comp (ref "H1203")
      (value "MOUNT-PAD-ROUND2.8")
      (footprint "eagle-import:2,8-PAD")
      (libsource (lib "eagle-import") (part "MOUNT-PAD-ROUND2.8"))
    )
    (comp (ref "H1204")
      (value "MOUNT-PAD-ROUND2.8")
      (footprint "eagle-import:2,8-PAD")
      (libsource (lib "eagle-import") (part "MOUNT-PAD-ROUND2.8"))
    )
    (comp (ref "C301")
      (value "100nF")
      (footprint "eagle-import:C0603")
      (libsource (lib "eagle-import") (part "C-EUC0603"))
    )
    (comp (ref "C302")
      (value "100nF")
      (footprint "eagle-import:C0603")
      (libsource (lib "eagle-import") (part "C-EUC0603"))
    )
    (comp (ref "R301")
      (value "68R")
      (footprint "eagle-import:R0603")
      (libsource (lib "eagle-import") (part "R-EU_R0603"))
    )
    (comp (ref "U301")
      (value "MPU-9250")
      (footprint "eagle-import:QFN24-3X3")
      (libsource (lib "eagle-import") (part "MPU-9250"))
    )
    (comp (ref "C901")
      (value "100uF")
      (footprint "eagle-import:C0805")
      (libsource (lib "eagle-import") (part "C-EUC0805"))
    )
    (comp (ref "J901")
      (value "JST_S3B-XH-A")
      (footprint "eagle-import:JST_S3B-XH-A")
      (libsource (lib "eagle-import") (part "JST_S3B-XH-A"))
    )
    (comp (ref "RPOLY901")
      (value "1.1A/2.2A")
      (footprint "eagle-import:M1206")
      (libsource (lib "eagle-import") (part "R-EU_M1206"))
    )
    (comp (ref "C1001")
      (value "100nF")
      (footprint "eagle-import:C0603")
      (libsource (lib "eagle-import") (part "C-EUC0603"))
    )
    (comp (ref "C1002")
      (value "100nF")
      (footprint "eagle-import:C0603")
      (libsource (lib "eagle-import") (part "C-EUC0603"))
    )
    (comp (ref "C1011")
      (value "100pF")
      (footprint "eagle-import:C0603")
      (libsource (lib "eagle-import") (part "C-EUC0603"))
    )
    (comp (ref "C1012")
      (value "100nF")
      (footprint "eagle-import:C0603")
      (libsource (lib "eagle-import") (part "C-EUC0603"))
    )
    (comp (ref "R1001")
      (value "100kR")
      (footprint "eagle-import:R0603")
      (libsource (lib "eagle-import") (part "R-EU_R0603"))
    )
    (comp (ref "R1002")
      (value "10kR")
      (footprint "eagle-import:R0603")
      (libsource (lib "eagle-import") (part "R-EU_R0603"))
    )
    (comp (ref "R1011")
      (value "100kR")
      (footprint "eagle-import:R0603")
      (libsource (lib "eagle-import") (part "R-EU_R0603"))
    )
    (comp (ref "R1012")
      (value "470kR")
      (footprint "eagle-import:R0603")
      (libsource (lib "eagle-import") (part "R-EU_R0603"))
    )
    (comp (ref "R1013")
      (value "47R")
      (footprint "eagle-import:R0603")
      (libsource (lib "eagle-import") (part "R-EU_R0603"))
    )
    (comp (ref "R1021")
      (value "27R")
      (footprint "eagle-import:R0603")
      (libsource (lib "eagle-import") (part "R-EU_R0603"))
    )
    (comp (ref "U1001")
      (value "CFPT-141-20MHZ")
      (footprint "eagle-import:CFPT-141")
      (fields (field (name "MF") "IQD-FREQUENCY-PRODUCTS") (field (name "MPN") "LFTVXO022175"))
      (libsource (lib "eagle-import") (part "CFPT-141-20MHZ"))
    )
    (comp (ref "U1011")
      (value "OPA354")
      (footprint "eagle-import:SOT-23-5")
      (fields (field (name "MPN") "OPA354AIDBVT"))
      (libsource (lib "eagle-import") (part "OPA354"))
    )
    (comp (ref "U1021")
      (value "OPA354")
      (footprint "eagle-import:SOT-23-5")
      (fields (field (name "MPN") "OPA354AIDBVT"))
      (libsource (lib "eagle-import") (part "OPA354"))
    )
    (comp (ref "C601")
      (value "100nF")
      (footprint "eagle-import:C0603")
      (libsource (lib "eagle-import") (part "C-EUC0603"))
    )
    (comp (ref "C611")
      (value "100nF")
      (footprint "eagle-import:C0603")
      (libsource (lib "eagle-import") (part "C-EUC0603"))
    )
    (comp (ref "C612")
      (value "100nF")
      (footprint "eagle-import:C0603")
      (libsource (lib "eagle-import") (part "C-EUC0603"))
    )
    (comp (ref "C681")
      (value "68pF")
      (footprint "eagle-import:C0603")
      (libsource (lib "eagle-import") (part "C-EUC0603"))
    )
    (comp (ref "C686")
      (value "18pF")
      (footprint "eagle-import:C0603")
      (libsource (lib "eagle-import") (part "C-EUC0603"))
    )
    (comp (ref "J685")
      (value "SMA_CON")
      (footprint "eagle-import:SMA_SMT_AMPHENOL_901-143")
      (fields (field (name "MPN") "901-143"))
      (libsource (lib "eagle-import") (part "SMA_SMT_AMPHENOL-901-143"))
    )
    (comp (ref "L671")
      (value "22nH")
      (footprint "eagle-import:R0603")
      (libsource (lib "eagle-import") (part "R-EU_R0603"))
    )
    (comp (ref "L681")
      (value "150nH")
      (footprint "eagle-import:R0603")
      (libsource (lib "eagle-import") (part "R-EU_R0603"))
    )
    (comp (ref "L682")
      (value "68nH")
      (footprint "eagle-import:R0603")
      (libsource (lib "eagle-import") (part "R-EU_R0603"))
    )
    (comp (ref "L686")
      (value "150nH")
      (footprint "eagle-import:R0603")
      (libsource (lib "eagle-import") (part "R-EU_R0603"))
    )
    (comp (ref "Q651")
      (value "ABM3B-16MHZ-10-R50-1-U")
      (footprint "eagle-import:CTS406")
      (libsource (lib "eagle-import") (part "CRYSTALCTS406"))
    )
    (comp (ref "U601")
      (value "AX5243")
      (footprint "eagle-import:QFN20-4X4-0P5-PAD")
      (libsource (lib "eagle-import") (part "AX5243"))
    )
    (comp (ref "C501")
      (value "100nF")
      (footprint "eagle-import:C0603")
      (libsource (lib "eagle-import") (part "C-EUC0603"))
    )
    (comp (ref "U501")
      (value "SHT31-DIS")
      (footprint "eagle-import:DFN8_SHT")
      (libsource (lib "eagle-import") (part "SHT31-DIS"))
    )
    (comp (ref "C401")
      (value "100nF")
      (footprint "eagle-import:C0603")
      (libsource (lib "eagle-import") (part "C-EUC0603"))
    )
    (comp (ref "R401")
      (value "10kR")
      (footprint "eagle-import:R0603")
      (libsource (lib "eagle-import") (part "R-EU_R0603"))
    )
    (comp (ref "R402")
      (value "10kR")
      (footprint "eagle-import:R0603")
      (libsource (lib "eagle-import") (part "R-EU_R0603"))
    )
    (comp (ref "U401")
      (value "MS5607-02BA03")
      (footprint "eagle-import:MS5607-02BA")
      (libsource (lib "eagle-import") (part "MS5607-02BA03"))
    )
    (comp (ref "C201")
      (value "100pF")
      (footprint "eagle-import:C0603")
      (libsource (lib "eagle-import") (part "C-EUC0603"))
    )
    (comp (ref "C251")
      (value "100pF")
      (footprint "eagle-import:C0603")
      (libsource (lib "eagle-import") (part "C-EUC0603"))
    )
    (comp (ref "C271")
      (value "C-EUC0603")
      (footprint "eagle-import:C0603")
      (libsource (lib "eagle-import") (part "C-EUC0603"))
    )
    (comp (ref "C272")
      (value "C-EUC0603")
      (footprint "eagle-import:C0603")
      (libsource (lib "eagle-import") (part "C-EUC0603"))
    )
    (comp (ref "C281")
      (value "C-EUC0603")
      (footprint "eagle-import:C0603")
      (libsource (lib "eagle-import") (part "C-EUC0603"))
    )
    (comp (ref "C282")
      (value "C-EUC0603")
      (footprint "eagle-import:C0603")
      (libsource (lib "eagle-import") (part "C-EUC0603"))
    )
    (comp (ref "C291")
      (value "C-EUC0603")
      (footprint "eagle-import:C0603")
      (libsource (lib "eagle-import") (part "C-EUC0603"))
    )
    (comp (ref "C292")
      (value "C-EUC0603")
      (footprint "eagle-import:C0603")
      (libsource (lib "eagle-import") (part "C-EUC0603"))
    )
    (comp (ref "D201")
      (value "BZX84-5V1")
      (footprint "eagle-import:TO236")
      (libsource (lib "eagle-import") (part "BZX84CSMD"))
    )
    (comp (ref "J291")
      (value "MCX-J-P-X-RA-SM1")
      (footprint "eagle-import:MCX-J-P-X-RA-SM1")
      (libsource (lib "eagle-import") (part "MCX-J-P-X-RA-SM1"))
    )
    (comp (ref "JP201")
      (value "POW")
      (footprint "eagle-import:1X02")
      (libsource (lib "eagle-import") (part "HEADER-1X2"))
    )
    (comp (ref "L291")
      (value "WE-CBF_300R")
      (footprint "eagle-import:L3216C")
      (libsource (lib "eagle-import") (part "L-EUL3216C"))
    )
    (comp (ref "R211")
      (value "10kR")
      (footprint "eagle-import:R0603")
      (libsource (lib "eagle-import") (part "R-EU_R0603"))
    )
    (comp (ref "R212")
      (value "10kR")
      (footprint "eagle-import:R0603")
      (libsource (lib "eagle-import") (part "R-EU_R0603"))
    )
    (comp (ref "R221")
      (value "68R")
      (footprint "eagle-import:R0603")
      (libsource (lib "eagle-import") (part "R-EU_R0603"))
    )
    (comp (ref "R222")
      (value "68R")
      (footprint "eagle-import:R0603")
      (libsource (lib "eagle-import") (part "R-EU_R0603"))
    )
    (comp (ref "R223")
      (value "68R")
      (footprint "eagle-import:R0603")
      (libsource (lib "eagle-import") (part "R-EU_R0603"))
    )
    (comp (ref "R224")
      (value "68R")
      (footprint "eagle-import:R0603")
      (libsource (lib "eagle-import") (part "R-EU_R0603"))
    )
    (comp (ref "R231")
      (value "68R")
      (footprint "eagle-import:R0603")
      (libsource (lib "eagle-import") (part "R-EU_R0603"))
    )
    (comp (ref "R232")
      (value "68R")
      (footprint "eagle-import:R0603")
      (libsource (lib "eagle-import") (part "R-EU_R0603"))
    )
    (comp (ref "R233")
      (value "68R")
      (footprint "eagle-import:R0603")
      (libsource (lib "eagle-import") (part "R-EU_R0603"))
    )
    (comp (ref "R234")
      (value "68R")
      (footprint "eagle-import:R0603")
      (libsource (lib "eagle-import") (part "R-EU_R0603"))
    )
    (comp (ref "R241")
      (value "68R")
      (footprint "eagle-import:R0603")
      (libsource (lib "eagle-import") (part "R-EU_R0603"))
    )
    (comp (ref "R251")
      (value "68R")
      (footprint "eagle-import:R0603")
      (libsource (lib "eagle-import") (part "R-EU_R0603"))
    )
    (comp (ref "R271")
      (value "R-EU_R0603")
      (footprint "eagle-import:R0603")
      (libsource (lib "eagle-import") (part "R-EU_R0603"))
    )
    (comp (ref "R281")
      (value "R-EU_R0603")
      (footprint "eagle-import:R0603")
      (libsource (lib "eagle-import") (part "R-EU_R0603"))
    )
    (comp (ref "R291")
      (value "R-EU_R0603")
      (footprint "eagle-import:R0603")
      (libsource (lib "eagle-import") (part "R-EU_R0603"))
    )
    (comp (ref "RPOLY291")
      (value "50mA/150mA")
      (footprint "eagle-import:R1210")
      (libsource (lib "eagle-import") (part "R-EU_R1210"))
    )
    (comp (ref "U201")
      (value "SIM808")
      (footprint "eagle-import:SIM808")
      (libsource (lib "eagle-import") (part "SIM808"))
    )
    (comp (ref "C701")
      (value "1nF")
      (footprint "eagle-import:C0603")
      (libsource (lib "eagle-import") (part "C-EUC0603"))
    )
    (comp (ref "C711")
      (value "100nF")
      (footprint "eagle-import:C0603")
      (libsource (lib "eagle-import") (part "C-EUC0603"))
    )
    (comp (ref "C712")
      (value "47uF")
      (footprint "eagle-import:C0805")
      (libsource (lib "eagle-import") (part "C-EUC0805"))
    )
    (comp (ref "D721")
      (value "BZX84-3V6")
      (footprint "eagle-import:TO236")
      (libsource (lib "eagle-import") (part "BZX84CSMD"))
    )
    (comp (ref "D722")
      (value "BZX84-3V6")
      (footprint "eagle-import:TO236")
      (libsource (lib "eagle-import") (part "BZX84CSMD"))
    )
    (comp (ref "J701")
      (value "MOLEX_105017-0001")
      (footprint "eagle-import:USB-B-MICRO-SMD_MOLEX-105017-0001")
      (libsource (lib "eagle-import") (part "USB_MICRO-B_MOLEX"))
    )
    (comp (ref "R701")
      (value "330kR")
      (footprint "eagle-import:R0603")
      (libsource (lib "eagle-import") (part "R-EU_R0603"))
    )
    (comp (ref "R721")
      (value "1.5kR")
      (footprint "eagle-import:R0603")
      (libsource (lib "eagle-import") (part "R-EU_R0603"))
    )
    (comp (ref "R722")
      (value "68R")
      (footprint "eagle-import:R0603")
      (libsource (lib "eagle-import") (part "R-EU_R0603"))
    )
    (comp (ref "R723")
      (value "68R")
      (footprint "eagle-import:R0603")
      (libsource (lib "eagle-import") (part "R-EU_R0603"))
    )
    (comp (ref "R724")
      (value "1MR")
      (footprint "eagle-import:R0603")
      (libsource (lib "eagle-import") (part "R-EU_R0603"))
    )
    (comp (ref "R725")
      (value "68R")
      (footprint "eagle-import:R0603")
      (libsource (lib "eagle-import") (part "R-EU_R0603"))
    )
    (comp (ref "RPOLY711")
      (value "0.5A/1.0A")
      (footprint "eagle-import:M1206")
      (libsource (lib "eagle-import") (part "R-EU_M1206"))
    )
    (comp (ref "C191")
      (value "100nF")
      (footprint "eagle-import:C0603")
      (libsource (lib "eagle-import") (part "C-EUC0603"))
    )
    (comp (ref "C192")
      (value "100nF")
      (footprint "eagle-import:C0603")
      (libsource (lib "eagle-import") (part "C-EUC0603"))
    )
    (comp (ref "C193")
      (value "100nF")
      (footprint "eagle-import:C0603")
      (libsource (lib "eagle-import") (part "C-EUC0603"))
    )
    (comp (ref "C194")
      (value "100nF")
      (footprint "eagle-import:C0603")
      (libsource (lib "eagle-import") (part "C-EUC0603"))
    )
    (comp (ref "C195")
      (value "100nF")
      (footprint "eagle-import:C0603")
      (libsource (lib "eagle-import") (part "C-EUC0603"))
    )
    (comp (ref "C196")
      (value "100nF")
      (footprint "eagle-import:C0603")
      (libsource (lib "eagle-import") (part "C-EUC0603"))
    )
    (comp (ref "C1111")
      (value "47uF")
      (footprint "eagle-import:C0805")
      (libsource (lib "eagle-import") (part "C-EUC0805"))
    )
    (comp (ref "C1112")
      (value "100nF")
      (footprint "eagle-import:C0603")
      (libsource (lib "eagle-import") (part "C-EUC0603"))
    )
    (comp (ref "C1113")
      (value "47uF")
      (footprint "eagle-import:C0805")
      (libsource (lib "eagle-import") (part "C-EUC0805"))
    )
    (comp (ref "C1121")
      (value "100nF")
      (footprint "eagle-import:C0603")
      (libsource (lib "eagle-import") (part "C-EUC0603"))
    )
    (comp (ref "D1111")
      (value "CRS08")
      (footprint "eagle-import:SOD80C")
      (libsource (lib "eagle-import") (part "CRS08"))
    )
    (comp (ref "D1121")
      (value "CRS08")
      (footprint "eagle-import:SOD80C")
      (libsource (lib "eagle-import") (part "CRS08"))
    )
    (comp (ref "D1122")
      (value "CRS08")
      (footprint "eagle-import:SOD80C")
      (libsource (lib "eagle-import") (part "CRS08"))
    )
    (comp (ref "L191")
      (value "10uH")
      (footprint "eagle-import:R0603")
      (libsource (lib "eagle-import") (part "R-EU_R0603"))
    )
    (comp (ref "L1111")
      (value "4.7uH")
      (footprint "eagle-import:L5650M")
      (libsource (lib "eagle-import") (part "L-EUL5650M"))
    )
    (comp (ref "R1111")
      (value "4.02kR")
      (footprint "eagle-import:R0603")
      (libsource (lib "eagle-import") (part "R-EU_R0603"))
    )
    (comp (ref "R1112")
      (value "6.04kR")
      (footprint "eagle-import:R0603")
      (libsource (lib "eagle-import") (part "R-EU_R0603"))
    )
    (comp (ref "R1113")
      (value "100kR")
      (footprint "eagle-import:R0603")
      (libsource (lib "eagle-import") (part "R-EU_R0603"))
    )
    (comp (ref "R1114")
      (value "15kR")
      (footprint "eagle-import:R0603")
      (libsource (lib "eagle-import") (part "R-EU_R0603"))
    )
    (comp (ref "R1115")
      (value "68kR")
      (footprint "eagle-import:R0603")
      (libsource (lib "eagle-import") (part "R-EU_R0603"))
    )
    (comp (ref "R1131")
      (value "4.02kR")
      (footprint "eagle-import:R0603")
      (libsource (lib "eagle-import") (part "R-EU_R0603"))
    )
    (comp (ref "R1132")
      (value "6.04kR")
      (footprint "eagle-import:R0603")
      (libsource (lib "eagle-import") (part "R-EU_R0603"))
    )
    (comp (ref "R1141")
      (value "4.02kR")
      (footprint "eagle-import:R0603")
      (libsource (lib "eagle-import") (part "R-EU_R0603"))
    )
    (comp (ref "R1142")
      (value "2.0kR")
      (footprint "eagle-import:R0603")
      (libsource (lib "eagle-import") (part "R-EU_R0603"))
    )
    (comp (ref "U1111")
      (value "LM2831YMF")
      (footprint "eagle-import:SOT95P280X145-5N")
      (fields (field (name "MPN") "LM2831YMF/NOPB"))
      (libsource (lib "eagle-import") (part "LM2831YMF"))
    )
    (comp (ref "U1121")
      (value "LM4120IM5-3.0")
      (footprint "eagle-import:SOT95P285X120-5N")
      (libsource (lib "eagle-import") (part "LM4120IM5-3.0"))
    )
    (comp (ref "J801")
      (value "MICROSIM-8P_SDCARD-8P_MOLEX-104642-1610")
      (footprint "eagle-import:MICROSIM-8P_SDCARD-8P_MOLEX-104642-1610")
      (fields (field (name "MPN") "MOLEX-104642-1610"))
      (libsource (lib "eagle-import") (part "MICROSIM-8P_SDCARD-8P_MOLEX-104642-1610"))
    )
  )
  (nets
    (net (code "1") (name "+3V0") (class "Default")
      (node (ref "C1002") (pin "1") (pinfunction "1_1") (pintype "passive"))
      (node (ref "C101") (pin "1") (pinfunction "1_1") (pintype "passive"))
      (node (ref "C251") (pin "1") (pinfunction "1_1") (pintype "passive"))
      (node (ref "R1142") (pin "2") (pinfunction "2_2") (pintype "passive"))
      (node (ref "U1001") (pin "4") (pinfunction "VCC_3V0_4") (pintype "power_in"))
      (node (ref "U101") (pin "51") (pinfunction "VBAT_51") (pintype "power_in"))
      (node (ref "U1121") (pin "5") (pinfunction "VOUT_5") (pintype "power_in"))
      (node (ref "U201") (pin "P$17") (pinfunction "VRTC_P$17") (pintype "power_in"))
    )
    (net (code "2") (name "+3V3") (class "Default")
      (node (ref "C1012") (pin "1") (pinfunction "1_1") (pintype "passive"))
      (node (ref "C1112") (pin "1") (pinfunction "1_1") (pintype "passive"))
      (node (ref "C1113") (pin "1") (pinfunction "1_1") (pintype "passive"))
      (node (ref "C191") (pin "1") (pinfunction "1_1") (pintype "passive"))
      (node (ref "C192") (pin "1") (pinfunction "1_1") (pintype "passive"))
      (node (ref "C193") (pin "1") (pinfunction "1_1") (pintype "passive"))
      (node (ref "C194") (pin "1") (pinfunction "1_1") (pintype "passive"))
      (node (ref "C195") (pin "1") (pinfunction "1_1") (pintype "passive"))
      (node (ref "C301") (pin "1") (pinfunction "1_1") (pintype "passive"))
      (node (ref "C401") (pin "1") (pinfunction "1_1") (pintype "passive"))
      (node (ref "C501") (pin "1") (pinfunction "1_1") (pintype "passive"))
      (node (ref "C601") (pin "1") (pinfunction "1_1") (pintype "passive"))
      (node (ref "JP111") (pin "7") (pinfunction "7_7") (pintype "passive"))
      (node (ref "JP121") (pin "5") (pinfunction "5_5") (pintype "passive"))
      (node (ref "JP131") (pin "2") (pinfunction "2_2") (pintype "passive"))
      (node (ref "L1111") (pin "1") (pinfunction "1_1") (pintype "passive"))
      (node (ref "L191") (pin "2") (pinfunction "2_2") (pintype "passive"))
      (node (ref "R1012") (pin "2") (pinfunction "2_2") (pintype "passive"))
      (node (ref "R111") (pin "2") (pinfunction "2_2") (pintype "passive"))
      (node (ref "R1115") (pin "2") (pinfunction "2_2") (pintype "passive"))
      (node (ref "R112") (pin "2") (pinfunction "2_2") (pintype "passive"))
      (node (ref "R211") (pin "1") (pinfunction "1_1") (pintype "passive"))
      (node (ref "R212") (pin "1") (pinfunction "1_1") (pintype "passive"))
      (node (ref "R401") (pin "2") (pinfunction "2_2") (pintype "passive"))
      (node (ref "R402") (pin "2") (pinfunction "2_2") (pintype "passive"))
      (node (ref "RPOLY291") (pin "2") (pinfunction "2_2") (pintype "passive"))
      (node (ref "U101") (pin "15") (pinfunction "VCC_1_15") (pintype "power_in"))
      (node (ref "U101") (pin "25") (pinfunction "VCC_2_25") (pintype "power_in"))
      (node (ref "U101") (pin "35") (pinfunction "VCC_3_35") (pintype "power_in"))
      (node (ref "U101") (pin "45") (pinfunction "VCC_4_45") (pintype "power_in"))
      (node (ref "U101") (pin "53") (pinfunction "VCC_5_53") (pintype "power_in"))
      (node (ref "U1011") (pin "5") (pinfunction "V+_5") (pintype "power_in"))
      (node (ref "U1021") (pin "5") (pinfunction "V+_5") (pintype "power_in"))
      (node (ref "U301") (pin "1") (pinfunction "VDDIO_1") (pintype "power_in"))
      (node (ref "U301") (pin "13") (pinfunction "VDD_13") (pintype "power_in"))
      (node (ref "U301") (pin "22") (pinfunction "~{CS}_22") (pintype "input"))
      (node (ref "U301") (pin "8") (pinfunction "VDDIO_8") (pintype "power_in"))
      (node (ref "U401") (pin "1") (pinfunction "VDD_1") (pintype "power_in"))
      (node (ref "U401") (pin "2") (pinfunction "PS_2") (pintype "input"))
      (node (ref "U401") (pin "4") (pinfunction "CSB_~{ADDR}_4") (pintype "input"))
      (node (ref "U501") (pin "5") (pinfunction "VDD_5") (pintype "power_in"))
      (node (ref "U601") (pin "16") (pinfunction "VDD_IO_16") (pintype "power_in"))
    )
    (net (code "3") (name "+5V") (class "Default")
      (node (ref "C711") (pin "1") (pinfunction "1_1") (pintype "passive"))
      (node (ref "C712") (pin "1") (pinfunction "1_1") (pintype "passive"))
      (node (ref "D1121") (pin "A") (pinfunction "A_A") (pintype "passive"))
      (node (ref "JP121") (pin "3") (pinfunction "3_3") (pintype "passive"))
      (node (ref "JP201") (pin "1") (pinfunction "1_1") (pintype "passive"))
      (node (ref "R1112") (pin "2") (pinfunction "2_2") (pintype "passive"))
      (node (ref "RPOLY711") (pin "2") (pinfunction "2_2") (pintype "passive"))
    )
    (net (code "4") (name "AD_3V0") (class "Default")
      (node (ref "R1141") (pin "2") (pinfunction "2_2") (pintype "passive"))
      (node (ref "R1142") (pin "1") (pinfunction "1_1") (pintype "passive"))
      (node (ref "U101") (pin "62") (pinfunction "PA0_62") (pintype "bidirectional"))
    )
    (net (code "5") (name "AD_5V0") (class "Default")
      (node (ref "R1111") (pin "2") (pinfunction "2_2") (pintype "passive"))
      (node (ref "R1112") (pin "1") (pinfunction "1_1") (pintype "passive"))
      (node (ref "U101") (pin "64") (pinfunction "PA2_64") (pintype "bidirectional"))
    )
    (net (code "6") (name "AD_VBAT") (class "Default")
      (node (ref "R1131") (pin "1") (pinfunction "1_1") (pintype "passive"))
      (node (ref "R1132") (pin "2") (pinfunction "2_2") (pintype "passive"))
      (node (ref "U101") (pin "1") (pinfunction "PA3_1") (pintype "bidirectional"))
    )
    (net (code "7") (name "AD_VCTCXO") (class "Default")
      (node (ref "R1021") (pin "2") (pinfunction "2_2") (pintype "passive"))
      (node (ref "U101") (pin "63") (pinfunction "PA1_63") (pintype "bidirectional"))
      (node (ref "U1021") (pin "1") (pinfunction "OUT_1") (pintype "output"))
    )
    (net (code "8") (name "AVCC") (class "Default")
      (node (ref "C196") (pin "1") (pinfunction "1_1") (pintype "passive"))
      (node (ref "L191") (pin "1") (pinfunction "1_1") (pintype "passive"))
      (node (ref "U101") (pin "61") (pinfunction "AVCC_61") (pintype "power_in"))
    )
    (net (code "9") (name "AX_ANT") (class "Default")
      (node (ref "C686") (pin "2") (pinfunction "2_2") (pintype "passive"))
      (node (ref "J685") (pin "1") (pinfunction "1_1") (pintype "passive"))
      (node (ref "L682") (pin "2") (pinfunction "2_2") (pintype "passive"))
    )
    (net (code "10") (name "AX_ANTN") (class "Default")
      (node (ref "C686") (pin "1") (pinfunction "1_1") (pintype "passive"))
      (node (ref "L686") (pin "2") (pinfunction "2_2") (pintype "passive"))
      (node (ref "U601") (pin "4") (pinfunction "ANTN_4") (pintype "passive"))
    )
    (net (code "11") (name "AX_ANTP") (class "Default")
      (node (ref "C681") (pin "1") (pinfunction "1_1") (pintype "passive"))
      (node (ref "L681") (pin "1") (pinfunction "1_1") (pintype "passive"))
      (node (ref "U601") (pin "3") (pinfunction "ANTP_3") (pintype "passive"))
    )
    (net (code "12") (name "AX_ANT_I") (class "Default")
      (node (ref "C681") (pin "2") (pinfunction "2_2") (pintype "passive"))
      (node (ref "L682") (pin "1") (pinfunction "1_1") (pintype "passive"))
    )
    (net (code "13") (name "AX_CLK") (class "Default")
      (node (ref "U101") (pin "23") (pinfunction "PC7_23") (pintype "bidirectional"))
      (node (ref "U601") (pin "11") (pinfunction "CLK_11") (pintype "input"))
    )
    (net (code "14") (name "AX_IRQ") (class "Default")
      (node (ref "U101") (pin "19") (pinfunction "PC3_19") (pintype "bidirectional"))
      (node (ref "U601") (pin "14") (pinfunction "IRQ_14") (pintype "bidirectional"))
    )
    (net (code "15") (name "AX_L1") (class "Default")
      (node (ref "L671") (pin "1") (pinfunction "1_1") (pintype "passive"))
      (node (ref "U601") (pin "8") (pinfunction "L1_8") (pintype "passive"))
    )
    (net (code "16") (name "AX_L2") (class "Default")
      (node (ref "L671") (pin "2") (pinfunction "2_2") (pintype "passive"))
      (node (ref "U601") (pin "7") (pinfunction "L2_7") (pintype "passive"))
    )
    (net (code "17") (name "AX_MISO") (class "Default")
      (node (ref "U101") (pin "22") (pinfunction "PC6_22") (pintype "bidirectional"))
      (node (ref "U601") (pin "12") (pinfunction "MISO_12") (pintype "output"))
    )
    (net (code "18") (name "AX_MOSI") (class "Default")
      (node (ref "U101") (pin "21") (pinfunction "PC5_21") (pintype "bidirectional"))
      (node (ref "U601") (pin "13") (pinfunction "MOSI_13") (pintype "input"))
    )
    (net (code "19") (name "AX_SEL") (class "Default")
      (node (ref "U101") (pin "20") (pinfunction "PC4_20") (pintype "bidirectional"))
      (node (ref "U601") (pin "10") (pinfunction "SEL_10") (pintype "input"))
    )
    (net (code "20") (name "BT_ANT") (class "Default")
      (node (ref "C282") (pin "1") (pinfunction "1_1") (pintype "passive"))
      (node (ref "R281") (pin "2") (pinfunction "2_2") (pintype "passive"))
    )
    (net (code "21") (name "BT_RF") (class "Default")
      (node (ref "C281") (pin "1") (pinfunction "1_1") (pintype "passive"))
      (node (ref "R281") (pin "1") (pinfunction "1_1") (pintype "passive"))
      (node (ref "U201") (pin "P$53") (pinfunction "ANT_BT_P$53") (pintype "bidirectional"))
    )
    (net (code "22") (name "CTS1") (class "Default")
      (node (ref "R173") (pin "1") (pinfunction "1_1") (pintype "passive"))
      (node (ref "U101") (pin "55") (pinfunction "PF7_55") (pintype "bidirectional"))
    )
    (net (code "23") (name "DCD1") (class "Default")
      (node (ref "R171") (pin "1") (pinfunction "1_1") (pintype "passive"))
      (node (ref "U101") (pin "47") (pinfunction "PF1_47") (pintype "bidirectional"))
    )
    (net (code "24") (name "DTR1") (class "Default")
      (node (ref "R222") (pin "1") (pinfunction "1_1") (pintype "passive"))
      (node (ref "U101") (pin "46") (pinfunction "PF0_46") (pintype "bidirectional"))
    )
    (net (code "25") (name "EN") (class "Default")
      (node (ref "R1113") (pin "2") (pinfunction "2_2") (pintype "passive"))
      (node (ref "U1111") (pin "4") (pinfunction "EN_4") (pintype "input"))
    )
    (net (code "26") (name "FB") (class "Default")
      (node (ref "R1114") (pin "2") (pinfunction "2_2") (pintype "passive"))
      (node (ref "R1115") (pin "1") (pinfunction "1_1") (pintype "passive"))
      (node (ref "U1111") (pin "3") (pinfunction "FB_3") (pintype "input"))
    )
    (net (code "27") (name "GND") (class "Default")
      (node (ref "C1001") (pin "2") (pinfunction "2_2") (pintype "passive"))
      (node (ref "C1002") (pin "2") (pinfunction "2_2") (pintype "passive"))
      (node (ref "C101") (pin "2") (pinfunction "2_2") (pintype "passive"))
      (node (ref "C1011") (pin "2") (pinfunction "2_2") (pintype "passive"))
      (node (ref "C1012") (pin "2") (pinfunction "2_2") (pintype "passive"))
      (node (ref "C1111") (pin "2") (pinfunction "2_2") (pintype "passive"))
      (node (ref "C1112") (pin "2") (pinfunction "2_2") (pintype "passive"))
      (node (ref "C1113") (pin "2") (pinfunction "2_2") (pintype "passive"))
      (node (ref "C1121") (pin "2") (pinfunction "2_2") (pintype "passive"))
      (node (ref "C141") (pin "2") (pinfunction "2_2") (pintype "passive"))
      (node (ref "C191") (pin "2") (pinfunction "2_2") (pintype "passive"))
      (node (ref "C192") (pin "2") (pinfunction "2_2") (pintype "passive"))
      (node (ref "C193") (pin "2") (pinfunction "2_2") (pintype "passive"))
      (node (ref "C194") (pin "2") (pinfunction "2_2") (pintype "passive"))
      (node (ref "C195") (pin "2") (pinfunction "2_2") (pintype "passive"))
      (node (ref "C196") (pin "2") (pinfunction "2_2") (pintype "passive"))
      (node (ref "C201") (pin "2") (pinfunction "2_2") (pintype "passive"))
      (node (ref "C251") (pin "2") (pinfunction "2_2") (pintype "passive"))
      (node (ref "C271") (pin "2") (pinfunction "2_2") (pintype "passive"))
      (node (ref "C272") (pin "2") (pinfunction "2_2") (pintype "passive"))
      (node (ref "C281") (pin "2") (pinfunction "2_2") (pintype "passive"))
      (node (ref "C282") (pin "2") (pinfunction "2_2") (pintype "passive"))
      (node (ref "C291") (pin "2") (pinfunction "2_2") (pintype "passive"))
      (node (ref "C292") (pin "2") (pinfunction "2_2") (pintype "passive"))
      (node (ref "C301") (pin "2") (pinfunction "2_2") (pintype "passive"))
      (node (ref "C302") (pin "2") (pinfunction "2_2") (pintype "passive"))
      (node (ref "C401") (pin "2") (pinfunction "2_2") (pintype "passive"))
      (node (ref "C501") (pin "2") (pinfunction "2_2") (pintype "passive"))
      (node (ref "C601") (pin "2") (pinfunction "2_2") (pintype "passive"))
      (node (ref "C611") (pin "2") (pinfunction "2_2") (pintype "passive"))
      (node (ref "C612") (pin "2") (pinfunction "2_2") (pintype "passive"))
      (node (ref "C701") (pin "2") (pinfunction "2_2") (pintype "passive"))
      (node (ref "C711") (pin "2") (pinfunction "2_2") (pintype "passive"))
      (node (ref "C712") (pin "2") (pinfunction "2_2") (pintype "passive"))
      (node (ref "C901") (pin "2") (pinfunction "2_2") (pintype "passive"))
      (node (ref "D1111") (pin "A") (pinfunction "A_A") (pintype "passive"))
      (node (ref "D201") (pin "A") (pinfunction "A_A") (pintype "passive"))
      (node (ref "D721") (pin "A") (pinfunction "A_A") (pintype "passive"))
      (node (ref "D722") (pin "A") (pinfunction "A_A") (pintype "passive"))
      (node (ref "H1201") (pin "B2,8") (pinfunction "MOUNT_B2,8") (pintype "passive"))
      (node (ref "H1203") (pin "B2,8") (pinfunction "MOUNT_B2,8") (pintype "passive"))
      (node (ref "H1204") (pin "B2,8") (pinfunction "MOUNT_B2,8") (pintype "passive"))
      (node (ref "J291") (pin "2") (pinfunction "2_2") (pintype "passive"))
      (node (ref "J291") (pin "3") (pinfunction "3_3") (pintype "passive"))
      (node (ref "J291") (pin "4") (pinfunction "4_4") (pintype "passive"))
      (node (ref "J291") (pin "5") (pinfunction "5_5") (pintype "passive"))
      (node (ref "J685") (pin "2") (pinfunction "2_2") (pintype "passive"))
      (node (ref "J685") (pin "3") (pinfunction "2_3") (pintype "passive"))
      (node (ref "J685") (pin "4") (pinfunction "2_4") (pintype "passive"))
      (node (ref "J685") (pin "5") (pinfunction "2_5") (pintype "passive"))
      (node (ref "J701") (pin "GND") (pinfunction "GND_GND") (pintype "passive"))
      (node (ref "J801") (pin "G1") (pinfunction "SHIELD_G1") (pintype "passive"))
      (node (ref "J801") (pin "G2") (pinfunction "SHIELD_G2") (pintype "passive"))
      (node (ref "J801") (pin "G3") (pinfunction "SHIELD_G3") (pintype "passive"))
      (node (ref "J801") (pin "G4") (pinfunction "SHIELD_G4") (pintype "passive"))
      (node (ref "J801") (pin "G5") (pinfunction "SHIELD_G5") (pintype "passive"))
      (node (ref "J801") (pin "G6") (pinfunction "SHIELD_G6") (pintype "passive"))
      (node (ref "J801") (pin "G7") (pinfunction "SHIELD_G7") (pintype "passive"))
      (node (ref "J801") (pin "G8") (pinfunction "SHIELD_G8") (pintype "passive"))
      (node (ref "J801") (pin "S5") (pinfunction "S5_S5") (pintype "passive"))
      (node (ref "J801") (pin "T6") (pinfunction "T6_T6") (pintype "passive"))
      (node (ref "J901") (pin "3") (pinfunction "3_3") (pintype "passive"))
      (node (ref "JP111") (pin "10") (pinfunction "10_10") (pintype "passive"))
      (node (ref "JP111") (pin "2") (pinfunction "2_2") (pintype "passive"))
      (node (ref "JP121") (pin "1") (pinfunction "1_1") (pintype "passive"))
      (node (ref "JP121") (pin "6") (pinfunction "6_6") (pintype "passive"))
      (node (ref "JP131") (pin "6") (pinfunction "6_6") (pintype "passive"))
      (node (ref "JP181") (pin "1") (pinfunction "1_1") (pintype "passive"))
      (node (ref "L681") (pin "2") (pinfunction "2_2") (pintype "passive"))
      (node (ref "L686") (pin "1") (pinfunction "1_1") (pintype "passive"))
      (node (ref "R1011") (pin "1") (pinfunction "1_1") (pintype "passive"))
      (node (ref "R1111") (pin "1") (pinfunction "1_1") (pintype "passive"))
      (node (ref "R1114") (pin "1") (pinfunction "1_1") (pintype "passive"))
      (node (ref "R1131") (pin "2") (pinfunction "2_2") (pintype "passive"))
      (node (ref "R1141") (pin "1") (pinfunction "1_1") (pintype "passive"))
      (node (ref "R701") (pin "2") (pinfunction "2_2") (pintype "passive"))
      (node (ref "R724") (pin "2") (pinfunction "2_2") (pintype "passive"))
      (node (ref "U1001") (pin "2") (pinfunction "GND_2") (pintype "power_in"))
      (node (ref "U101") (pin "14") (pinfunction "GND_1_14") (pintype "passive"))
      (node (ref "U101") (pin "24") (pinfunction "GND_2_24") (pintype "passive"))
      (node (ref "U101") (pin "34") (pinfunction "GND_3_34") (pintype "passive"))
      (node (ref "U101") (pin "44") (pinfunction "GND_4_44") (pintype "passive"))
      (node (ref "U101") (pin "52") (pinfunction "GND_5_52") (pintype "passive"))
      (node (ref "U101") (pin "60") (pinfunction "GND_6_60") (pintype "passive"))
      (node (ref "U1011") (pin "2") (pinfunction "V-_2") (pintype "power_in"))
      (node (ref "U1021") (pin "2") (pinfunction "V-_2") (pintype "power_in"))
      (node (ref "U1111") (pin "2") (pinfunction "GND_2") (pintype "passive"))
      (node (ref "U1121") (pin "2") (pinfunction "GND_2") (pintype "passive"))
      (node (ref "U201") (pin "P$1") (pinfunction "GND_P$1") (pintype "power_in"))
      (node (ref "U201") (pin "P$18") (pinfunction "GND_P$18") (pintype "power_in"))
      (node (ref "U201") (pin "P$2") (pinfunction "GND_P$2") (pintype "power_in"))
      (node (ref "U201") (pin "P$28") (pinfunction "GND_P$28") (pintype "power_in"))
      (node (ref "U201") (pin "P$3") (pinfunction "GND_P$3") (pintype "power_in"))
      (node (ref "U201") (pin "P$34") (pinfunction "GND_P$34") (pintype "power_in"))
      (node (ref "U201") (pin "P$36") (pinfunction "GND_P$36") (pintype "power_in"))
      (node (ref "U201") (pin "P$40") (pinfunction "GND_P$40") (pintype "power_in"))
      (node (ref "U201") (pin "P$51") (pinfunction "GND_P$51") (pintype "power_in"))
      (node (ref "U201") (pin "P$52") (pinfunction "GND_P$52") (pintype "power_in"))
      (node (ref "U201") (pin "P$54") (pinfunction "GND_P$54") (pintype "power_in"))
      (node (ref "U201") (pin "P$64") (pinfunction "GND_P$64") (pintype "power_in"))
      (node (ref "U201") (pin "P$65") (pinfunction "GND_P$65") (pintype "power_in"))
      (node (ref "U201") (pin "P$67") (pinfunction "GND_P$67") (pintype "power_in"))
      (node (ref "U201") (pin "P$68") (pinfunction "GND_P$68") (pintype "power_in"))
      (node (ref "U301") (pin "11") (pinfunction "FSYNC_11") (pintype "passive"))
      (node (ref "U301") (pin "18") (pinfunction "GND_18") (pintype "passive"))
      (node (ref "U301") (pin "20") (pinfunction "GND_20") (pintype "passive"))
      (node (ref "U301") (pin "9") (pinfunction "AD0/SDO_9") (pintype "bidirectional"))
      (node (ref "U401") (pin "3") (pinfunction "GND_3") (pintype "passive"))
      (node (ref "U501") (pin "2") (pinfunction "ADDR_2") (pintype "input"))
      (node (ref "U501") (pin "6") (pinfunction "~{RESET}_6") (pintype "passive"))
      (node (ref "U501") (pin "7") (pinfunction "R_7") (pintype "passive"))
      (node (ref "U501") (pin "8") (pinfunction "VSS_8") (pintype "passive"))
      (node (ref "U501") (pin "9") (pinfunction "PAD_9") (pintype "passive"))
      (node (ref "U601") (pin "17") (pinfunction "GPADC1_17") (pintype "passive"))
      (node (ref "U601") (pin "18") (pinfunction "GPADC2_18") (pintype "passive"))
      (node (ref "U601") (pin "2") (pinfunction "GND_2") (pintype "power_in"))
      (node (ref "U601") (pin "21") (pinfunction "GND_21") (pintype "power_in"))
    )
    (net (code "28") (name "GPS_1PPS") (class "Default")
      (node (ref "R251") (pin "1") (pinfunction "1_1") (pintype "passive"))
      (node (ref "U101") (pin "58") (pinfunction "PR0_58") (pintype "bidirectional"))
    )
    (net (code "29") (name "GPS_1PPS_DRV") (class "Default")
      (node (ref "R251") (pin "2") (pinfunction "2_2") (pintype "passive"))
      (node (ref "U201") (pin "P$37") (pinfunction "1PPS_P$37") (pintype "output"))
    )
    (net (code "30") (name "GPS_ANT") (class "Default")
      (node (ref "C291") (pin "1") (pinfunction "1_1") (pintype "passive"))
      (node (ref "J291") (pin "1") (pinfunction "1_1") (pintype "passive"))
      (node (ref "L291") (pin "2") (pinfunction "2_2") (pintype "passive"))
      (node (ref "R291") (pin "1") (pinfunction "1_1") (pintype "passive"))
    )
    (net (code "31") (name "GPS_PWR") (class "Default")
      (node (ref "L291") (pin "1") (pinfunction "1_1") (pintype "passive"))
      (node (ref "RPOLY291") (pin "1") (pinfunction "1_1") (pintype "passive"))
    )
    (net (code "32") (name "GPS_RF_IN") (class "Default")
      (node (ref "C292") (pin "1") (pinfunction "1_1") (pintype "passive"))
      (node (ref "R291") (pin "2") (pinfunction "2_2") (pintype "passive"))
      (node (ref "U201") (pin "P$35") (pinfunction "GPS_RF_IN_P$35") (pintype "input"))
    )
    (net (code "33") (name "GSM_ANT") (class "Default")
      (node (ref "C272") (pin "1") (pinfunction "1_1") (pintype "passive"))
      (node (ref "R271") (pin "2") (pinfunction "2_2") (pintype "passive"))
    )
    (net (code "34") (name "GSM_CTS") (class "Default")
      (node (ref "R223") (pin "2") (pinfunction "2_2") (pintype "passive"))
      (node (ref "U201") (pin "P$12") (pinfunction "CTS_P$12") (pintype "output"))
    )
    (net (code "35") (name "GSM_DCD") (class "Default")
      (node (ref "R222") (pin "2") (pinfunction "2_2") (pintype "passive"))
      (node (ref "U201") (pin "P$11") (pinfunction "DCD_P$11") (pintype "output"))
    )
    (net (code "36") (name "GSM_DTR") (class "Default")
      (node (ref "R171") (pin "2") (pinfunction "2_2") (pintype "passive"))
      (node (ref "U201") (pin "P$9") (pinfunction "DTR_P$9") (pintype "input"))
    )
    (net (code "37") (name "GSM_NETLIGHT") (class "Default")
      (node (ref "R231") (pin "2") (pinfunction "2_2") (pintype "passive"))
      (node (ref "U101") (pin "5") (pinfunction "PA7_5") (pintype "bidirectional"))
    )
    (net (code "38") (name "GSM_NETLIGHT_DRV") (class "Default")
      (node (ref "R231") (pin "1") (pinfunction "1_1") (pintype "passive"))
      (node (ref "U201") (pin "P$50") (pinfunction "NETLIGHT_P$50") (pintype "output"))
    )
    (net (code "39") (name "GSM_PCM_CLK") (class "Default")
      (node (ref "R141") (pin "2") (pinfunction "2_2") (pintype "passive"))
      (node (ref "U201") (pin "P$46") (pinfunction "PCM_CLK_P$46") (pintype "input"))
    )
    (net (code "40") (name "GSM_PCM_CLK_DRV") (class "Default")
      (node (ref "R141") (pin "1") (pinfunction "1_1") (pintype "passive"))
      (node (ref "U101") (pin "27") (pinfunction "PD1_27") (pintype "bidirectional"))
    )
    (net (code "41") (name "GSM_PCM_IN") (class "Default")
      (node (ref "R142") (pin "2") (pinfunction "2_2") (pintype "passive"))
      (node (ref "U201") (pin "P$47") (pinfunction "PCM_IN_P$47") (pintype "input"))
    )
    (net (code "42") (name "GSM_PCM_IN_DRV") (class "Default")
      (node (ref "R142") (pin "1") (pinfunction "1_1") (pintype "passive"))
      (node (ref "U101") (pin "29") (pinfunction "PD3_29") (pintype "bidirectional"))
    )
    (net (code "43") (name "GSM_PCM_OUT") (class "Default")
      (node (ref "R233") (pin "2") (pinfunction "2_2") (pintype "passive"))
      (node (ref "U101") (pin "28") (pinfunction "PD2_28") (pintype "bidirectional"))
    )
    (net (code "44") (name "GSM_PCM_OUT_DRV") (class "Default")
      (node (ref "R233") (pin "1") (pinfunction "1_1") (pintype "passive"))
      (node (ref "U201") (pin "P$48") (pinfunction "PCM_OUT_P$48") (pintype "output"))
    )
    (net (code "45") (name "GSM_PCM_SYNC") (class "Default")
      (node (ref "R234") (pin "2") (pinfunction "2_2") (pintype "passive"))
      (node (ref "U101") (pin "26") (pinfunction "PD0_26") (pintype "bidirectional"))
    )
    (net (code "46") (name "GSM_PCM_SYNC_DRV") (class "Default")
      (node (ref "R234") (pin "1") (pinfunction "1_1") (pintype "passive"))
      (node (ref "U201") (pin "P$45") (pinfunction "PCM_SYNC_P$45") (pintype "output"))
    )
    (net (code "47") (name "GSM_PWRKEY") (class "Default")
      (node (ref "R162") (pin "2") (pinfunction "2_2") (pintype "passive"))
      (node (ref "U201") (pin "P$8") (pinfunction "PWRKEY_P$8") (pintype "input"))
    )
    (net (code "48") (name "GSM_RESET") (class "Default")
      (node (ref "R163") (pin "2") (pinfunction "2_2") (pintype "passive"))
      (node (ref "U201") (pin "P$16") (pinfunction "RESET_P$16") (pintype "input"))
    )
    (net (code "49") (name "GSM_RF") (class "Default")
      (node (ref "C271") (pin "1") (pinfunction "1_1") (pintype "passive"))
      (node (ref "R271") (pin "1") (pinfunction "1_1") (pintype "passive"))
      (node (ref "U201") (pin "P$66") (pinfunction "GSM_RF_IN_P$66") (pintype "bidirectional"))
    )
    (net (code "50") (name "GSM_RF_SYNC") (class "Default")
      (node (ref "C141") (pin "1") (pinfunction "1_1") (pintype "passive"))
      (node (ref "R241") (pin "2") (pinfunction "2_2") (pintype "passive"))
      (node (ref "U101") (pin "4") (pinfunction "PA6_4") (pintype "bidirectional"))
    )
    (net (code "51") (name "GSM_RF_SYNC_DRV") (class "Default")
      (node (ref "R241") (pin "1") (pinfunction "1_1") (pintype "passive"))
      (node (ref "U201") (pin "P$63") (pinfunction "RF_SYNC_P$63") (pintype "output"))
    )
    (net (code "52") (name "GSM_RI") (class "Default")
      (node (ref "R221") (pin "2") (pinfunction "2_2") (pintype "passive"))
      (node (ref "U201") (pin "P$10") (pinfunction "RI_P$10") (pintype "output"))
    )
    (net (code "53") (name "GSM_RTS") (class "Default")
      (node (ref "R173") (pin "2") (pinfunction "2_2") (pintype "passive"))
      (node (ref "U201") (pin "P$13") (pinfunction "RTS_P$13") (pintype "input"))
    )
    (net (code "54") (name "GSM_RXD") (class "Default")
      (node (ref "R172") (pin "2") (pinfunction "2_2") (pintype "passive"))
      (node (ref "U201") (pin "P$15") (pinfunction "RXD_P$15") (pintype "input"))
    )
    (net (code "55") (name "GSM_STATUS") (class "Default")
      (node (ref "R232") (pin "2") (pinfunction "2_2") (pintype "passive"))
      (node (ref "U101") (pin "38") (pinfunction "PE2_38") (pintype "bidirectional"))
    )
    (net (code "56") (name "GSM_STATUS_DRV") (class "Default")
      (node (ref "R232") (pin "1") (pinfunction "1_1") (pintype "passive"))
      (node (ref "U201") (pin "P$49") (pinfunction "STATUS_P$49") (pintype "output"))
    )
    (net (code "57") (name "GSM_TXD") (class "Default")
      (node (ref "R224") (pin "2") (pinfunction "2_2") (pintype "passive"))
      (node (ref "U201") (pin "P$14") (pinfunction "TXD_P$14") (pintype "output"))
    )
    (net (code "58") (name "GSM_VDD_EXT") (class "Default")
      (node (ref "R161") (pin "2") (pinfunction "2_2") (pintype "passive"))
      (node (ref "U201") (pin "P$7") (pinfunction "VDD_EXT(2.8VOUT)_P$7") (pintype "output"))
    )
    (net (code "59") (name "I2C2_INT") (class "Default")
      (node (ref "R301") (pin "2") (pinfunction "2_2") (pintype "passive"))
      (node (ref "U101") (pin "6") (pinfunction "PB0_6") (pintype "bidirectional"))
    )
    (net (code "60") (name "IO_ADC4") (class "Default")
      (node (ref "JP181") (pin "3") (pinfunction "3_3") (pintype "passive"))
      (node (ref "U101") (pin "2") (pinfunction "PA4_2") (pintype "bidirectional"))
    )
    (net (code "61") (name "IO_ADC5") (class "Default")
      (node (ref "JP181") (pin "5") (pinfunction "5_5") (pintype "passive"))
      (node (ref "U101") (pin "3") (pinfunction "PA5_3") (pintype "bidirectional"))
    )
    (net (code "62") (name "IO_DAC0") (class "Default")
      (node (ref "JP181") (pin "4") (pinfunction "4_4") (pintype "passive"))
      (node (ref "U101") (pin "8") (pinfunction "PB2_8") (pintype "bidirectional"))
    )
    (net (code "63") (name "IO_DAC1") (class "Default")
      (node (ref "JP181") (pin "6") (pinfunction "6_6") (pintype "passive"))
      (node (ref "U101") (pin "9") (pinfunction "PB3_9") (pintype "bidirectional"))
    )
    (net (code "64") (name "IO_OC1A") (class "Default")
      (node (ref "JP181") (pin "2") (pinfunction "2_2") (pintype "passive"))
      (node (ref "U101") (pin "30") (pinfunction "PD4_30") (pintype "bidirectional"))
    )
    (net (code "65") (name "MPU_INT") (class "Default")
      (node (ref "R301") (pin "1") (pinfunction "1_1") (pintype "passive"))
      (node (ref "U301") (pin "12") (pinfunction "INT_12") (pintype "output"))
    )
    (net (code "66") (name "Net-(C611-Pad1)") (class "Default")
      (node (ref "C611") (pin "1") (pinfunction "1_1") (pintype "passive"))
      (node (ref "U601") (pin "1") (pinfunction "VDD_ANA_1") (pintype "passive"))
    )
    (net (code "67") (name "Net-(C612-Pad1)") (class "Default")
      (node (ref "C612") (pin "1") (pinfunction "1_1") (pintype "passive"))
      (node (ref "U601") (pin "5") (pinfunction "VDD_ANA_5") (pintype "passive"))
    )
    (net (code "68") (name "Net-(C701-Pad1)") (class "Default")
      (node (ref "C701") (pin "1") (pinfunction "1_1") (pintype "passive"))
      (node (ref "J701") (pin "JSHIELD") (pinfunction "SHIELD_JSHIELD") (pintype "passive"))
      (node (ref "J701") (pin "JSHIELD@2") (pinfunction "SHIELD_JSHIELD@2") (pintype "passive"))
      (node (ref "J701") (pin "JSHIELD@3") (pinfunction "SHIELD_JSHIELD@3") (pintype "passive"))
      (node (ref "J701") (pin "JSHIELD@4") (pinfunction "SHIELD_JSHIELD@4") (pintype "passive"))
      (node (ref "J701") (pin "JSHIELD@5") (pinfunction "SHIELD_JSHIELD@5") (pintype "passive"))
      (node (ref "J701") (pin "JSHIELD@6") (pinfunction "SHIELD_JSHIELD@6") (pintype "passive"))
      (node (ref "R701") (pin "1") (pinfunction "1_1") (pintype "passive"))
    )
    (net (code "69") (name "Net-(J701-J_D+)") (class "Default")
      (node (ref "J701") (pin "D+") (pinfunction "J_D+_D+") (pintype "bidirectional"))
      (node (ref "R723") (pin "1") (pinfunction "1_1") (pintype "passive"))
      (node (ref "R724") (pin "1") (pinfunction "1_1") (pintype "passive"))
    )
    (net (code "70") (name "Net-(J701-J_D-)") (class "Default")
      (node (ref "J701") (pin "D-") (pinfunction "J_D-_D-") (pintype "bidirectional"))
      (node (ref "R721") (pin "1") (pinfunction "1_1") (pintype "passive"))
      (node (ref "R722") (pin "1") (pinfunction "1_1") (pintype "passive"))
    )
    (net (code "71") (name "Net-(J701-J_ID)") (class "Default")
      (node (ref "J701") (pin "ID") (pinfunction "J_ID_ID") (pintype "bidirectional"))
      (node (ref "R725") (pin "1") (pinfunction "1_1") (pintype "passive"))
    )
    (net (code "72") (name "Net-(J701-J_VUSB)") (class "Default")
      (node (ref "J701") (pin "VBUS") (pinfunction "J_VUSB_VBUS") (pintype "power_in"))
      (node (ref "RPOLY711") (pin "1") (pinfunction "1_1") (pintype "passive"))
    )
    (net (code "73") (name "Net-(J901-Pad1)") (class "Default")
      (node (ref "J901") (pin "1") (pinfunction "1_1") (pintype "passive"))
      (node (ref "RPOLY901") (pin "1") (pinfunction "1_1") (pintype "passive"))
    )
    (net (code "74") (name "Net-(Q651-2)") (class "Default")
      (node (ref "Q651") (pin "3") (pinfunction "2_3") (pintype "passive"))
      (node (ref "U601") (pin "19") (pinfunction "CLK16N_19") (pintype "passive"))
    )
    (net (code "75") (name "Net-(U101A-TOSC1)") (class "Default")
      (node (ref "Q101") (pin "2") (pinfunction "2_2") (pintype "passive"))
      (node (ref "U101") (pin "43") (pinfunction "TOSC1_43") (pintype "passive"))
    )
    (net (code "76") (name "Net-(U101A-TOSC2)") (class "Default")
      (node (ref "Q101") (pin "1") (pinfunction "1_1") (pintype "passive"))
      (node (ref "U101") (pin "42") (pinfunction "TOSC2_42") (pintype "passive"))
    )
    (net (code "77") (name "Net-(U301-REGOUT)") (class "Default")
      (node (ref "C302") (pin "1") (pinfunction "1_1") (pintype "passive"))
      (node (ref "U301") (pin "10") (pinfunction "REGOUT_10") (pintype "passive"))
    )
    (net (code "78") (name "Net-(U601-CLK16P)") (class "Default")
      (node (ref "Q651") (pin "1") (pinfunction "1_1") (pintype "passive"))
      (node (ref "U601") (pin "20") (pinfunction "CLK16P_20") (pintype "passive"))
    )
    (net (code "79") (name "Net-(U1021--IN)") (class "Default")
      (node (ref "R1021") (pin "1") (pinfunction "1_1") (pintype "passive"))
      (node (ref "U1021") (pin "4") (pinfunction "-IN_4") (pintype "input"))
    )
    (net (code "80") (name "Net-(U1111-VIN)") (class "Default")
      (node (ref "C1111") (pin "1") (pinfunction "1_1") (pintype "passive"))
      (node (ref "C1121") (pin "1") (pinfunction "1_1") (pintype "passive"))
      (node (ref "D1121") (pin "C") (pinfunction "C_C") (pintype "passive"))
      (node (ref "D1122") (pin "C") (pinfunction "C_C") (pintype "passive"))
      (node (ref "R1113") (pin "1") (pinfunction "1_1") (pintype "passive"))
      (node (ref "U1111") (pin "5") (pinfunction "VIN_5") (pintype "power_in"))
      (node (ref "U1121") (pin "3") (pinfunction "EN_3") (pintype "input"))
      (node (ref "U1121") (pin "4") (pinfunction "VIN_4") (pintype "power_in"))
    )
    (net (code "81") (name "PDI_CLK") (class "Default")
      (node (ref "JP111") (pin "6") (pinfunction "6_6") (pintype "passive"))
      (node (ref "JP131") (pin "5") (pinfunction "5_5") (pintype "passive"))
      (node (ref "R112") (pin "1") (pinfunction "1_1") (pintype "passive"))
      (node (ref "R132") (pin "1") (pinfunction "1_1") (pintype "passive"))
    )
    (net (code "82") (name "PDI_CLK_CPU") (class "Default")
      (node (ref "R132") (pin "2") (pinfunction "2_2") (pintype "passive"))
      (node (ref "U101") (pin "57") (pinfunction "~{RESET}/PDI_CLK_57") (pintype "input"))
    )
    (net (code "83") (name "PDI_DATA") (class "Default")
      (node (ref "JP131") (pin "1") (pinfunction "1_1") (pintype "passive"))
      (node (ref "R131") (pin "1") (pinfunction "1_1") (pintype "passive"))
    )
    (net (code "84") (name "PDI_DATA_CPU") (class "Default")
      (node (ref "R131") (pin "2") (pinfunction "2_2") (pintype "passive"))
      (node (ref "U101") (pin "56") (pinfunction "PDI_DATA_56") (pintype "input"))
    )
    (net (code "85") (name "POWERED_GSM") (class "Default")
      (node (ref "R161") (pin "1") (pinfunction "1_1") (pintype "passive"))
      (node (ref "U101") (pin "39") (pinfunction "PE3_39") (pintype "bidirectional"))
    )
    (net (code "86") (name "PWRKEY_GSM") (class "Default")
      (node (ref "R162") (pin "1") (pinfunction "1_1") (pintype "passive"))
      (node (ref "U101") (pin "40") (pinfunction "PE4_40") (pintype "bidirectional"))
    )
    (net (code "87") (name "RESET_GSM") (class "Default")
      (node (ref "R163") (pin "1") (pinfunction "1_1") (pintype "passive"))
      (node (ref "U101") (pin "41") (pinfunction "PE5_41") (pintype "bidirectional"))
    )
    (net (code "88") (name "RI1") (class "Default")
      (node (ref "R221") (pin "1") (pinfunction "1_1") (pintype "passive"))
      (node (ref "U101") (pin "50") (pinfunction "PF4_50") (pintype "bidirectional"))
    )
    (net (code "89") (name "RTS1") (class "Default")
      (node (ref "R223") (pin "1") (pinfunction "1_1") (pintype "passive"))
      (node (ref "U101") (pin "54") (pinfunction "PF6_54") (pintype "bidirectional"))
    )
    (net (code "90") (name "RXD1") (class "Default")
      (node (ref "R224") (pin "1") (pinfunction "1_1") (pintype "passive"))
      (node (ref "U101") (pin "48") (pinfunction "PF2_48") (pintype "bidirectional"))
    )
    (net (code "91") (name "SCL1") (class "Default")
      (node (ref "R212") (pin "2") (pinfunction "2_2") (pintype "passive"))
      (node (ref "R401") (pin "1") (pinfunction "1_1") (pintype "passive"))
      (node (ref "U101") (pin "37") (pinfunction "PE1_37") (pintype "bidirectional"))
      (node (ref "U201") (pin "P$39") (pinfunction "SCL_P$39") (pintype "bidirectional"))
      (node (ref "U301") (pin "23") (pinfunction "SCL/SCLK_23") (pintype "input"))
      (node (ref "U401") (pin "8") (pinfunction "SCL_SCLK_8") (pintype "input"))
      (node (ref "U501") (pin "4") (pinfunction "SCL_4") (pintype "input"))
    )
    (net (code "92") (name "SCL2") (class "Default")
      (node (ref "JP121") (pin "2") (pinfunction "2_2") (pintype "passive"))
      (node (ref "U101") (pin "17") (pinfunction "PC1_17") (pintype "bidirectional"))
    )
    (net (code "93") (name "SDA1") (class "Default")
      (node (ref "R211") (pin "2") (pinfunction "2_2") (pintype "passive"))
      (node (ref "R402") (pin "1") (pinfunction "1_1") (pintype "passive"))
      (node (ref "U101") (pin "36") (pinfunction "PE0_36") (pintype "bidirectional"))
      (node (ref "U201") (pin "P$38") (pinfunction "SDA_P$38") (pintype "bidirectional"))
      (node (ref "U301") (pin "24") (pinfunction "SDA/SDI_24") (pintype "bidirectional"))
      (node (ref "U401") (pin "7") (pinfunction "SDI_SDA_7") (pintype "bidirectional"))
      (node (ref "U501") (pin "1") (pinfunction "SDA_1") (pintype "bidirectional"))
    )
    (net (code "94") (name "SDA2") (class "Default")
      (node (ref "JP121") (pin "4") (pinfunction "4_4") (pintype "passive"))
      (node (ref "U101") (pin "16") (pinfunction "PC0_16") (pintype "bidirectional"))
    )
    (net (code "95") (name "SIM_CLK") (class "Default")
      (node (ref "J801") (pin "S3") (pinfunction "S3_S3") (pintype "input"))
      (node (ref "U201") (pin "P$31") (pinfunction "SIM_CLK_P$31") (pintype "output"))
    )
    (net (code "96") (name "SIM_IO") (class "Default")
      (node (ref "J801") (pin "S7") (pinfunction "S7_S7") (pintype "bidirectional"))
      (node (ref "U201") (pin "P$30") (pinfunction "SIM_DATA_P$30") (pintype "bidirectional"))
    )
    (net (code "97") (name "SIM_RST") (class "Default")
      (node (ref "J801") (pin "S2") (pinfunction "S2_S2") (pintype "bidirectional"))
      (node (ref "U201") (pin "P$32") (pinfunction "SIM_RST_P$32") (pintype "output"))
    )
    (net (code "98") (name "SIM_VBUS") (class "Default")
      (node (ref "JP201") (pin "2") (pinfunction "2_2") (pintype "passive"))
      (node (ref "U201") (pin "P$25") (pinfunction "VBUS_P$25") (pintype "power_in"))
    )
    (net (code "99") (name "SIM_VCC") (class "Default")
      (node (ref "J801") (pin "S1") (pinfunction "S1_S1") (pintype "power_in"))
      (node (ref "U201") (pin "P$29") (pinfunction "SIM_VDD_P$29") (pintype "power_in"))
    )
    (net (code "100") (name "SIM_VPP") (class "Default")
      (node (ref "J801") (pin "S6") (pinfunction "S6_S6") (pintype "power_in"))
      (node (ref "U201") (pin "P$33") (pinfunction "SIM_PRE_P$33") (pintype "input"))
    )
    (net (code "101") (name "SW") (class "Default")
      (node (ref "D1111") (pin "C") (pinfunction "C_C") (pintype "passive"))
      (node (ref "L1111") (pin "2") (pinfunction "2_2") (pintype "passive"))
      (node (ref "U1111") (pin "1") (pinfunction "SW_1") (pintype "output"))
    )
    (net (code "102") (name "T4") (class "Default")
      (node (ref "J801") (pin "T4") (pinfunction "T4_T4") (pintype "power_in"))
    )
    (net (code "103") (name "TCK") (class "Default")
      (node (ref "JP111") (pin "1") (pinfunction "1_1") (pintype "passive"))
      (node (ref "U101") (pin "12") (pinfunction "PB6_12") (pintype "bidirectional"))
    )
    (net (code "104") (name "TCXO_20MHZ") (class "Default")
      (node (ref "R1013") (pin "2") (pinfunction "2_2") (pintype "passive"))
      (node (ref "U101") (pin "59") (pinfunction "PR1_59") (pintype "bidirectional"))
    )
    (net (code "105") (name "TDI") (class "Default")
      (node (ref "JP111") (pin "9") (pinfunction "9_9") (pintype "passive"))
      (node (ref "U101") (pin "11") (pinfunction "PB5_11") (pintype "bidirectional"))
    )
    (net (code "106") (name "TDO") (class "Default")
      (node (ref "JP111") (pin "3") (pinfunction "3_3") (pintype "passive"))
      (node (ref "U101") (pin "13") (pinfunction "PB7_13") (pintype "bidirectional"))
    )
    (net (code "107") (name "TMS") (class "Default")
      (node (ref "JP111") (pin "5") (pinfunction "5_5") (pintype "passive"))
      (node (ref "U101") (pin "10") (pinfunction "PB4_10") (pintype "bidirectional"))
    )
    (net (code "108") (name "TRSH") (class "Default")
      (node (ref "C1011") (pin "1") (pinfunction "1_1") (pintype "passive"))
      (node (ref "R1011") (pin "2") (pinfunction "2_2") (pintype "passive"))
      (node (ref "R1012") (pin "1") (pinfunction "1_1") (pintype "passive"))
      (node (ref "U1011") (pin "4") (pinfunction "-IN_4") (pintype "input"))
    )
    (net (code "109") (name "TXD1") (class "Default")
      (node (ref "R172") (pin "1") (pinfunction "1_1") (pintype "passive"))
      (node (ref "U101") (pin "49") (pinfunction "PF3_49") (pintype "bidirectional"))
    )
    (net (code "110") (name "USB_D_N") (class "Default")
      (node (ref "D722") (pin "C") (pinfunction "C_C") (pintype "passive"))
      (node (ref "R722") (pin "2") (pinfunction "2_2") (pintype "passive"))
      (node (ref "U101") (pin "32") (pinfunction "PD6_32") (pintype "bidirectional"))
    )
    (net (code "111") (name "USB_D_P") (class "Default")
      (node (ref "D721") (pin "C") (pinfunction "C_C") (pintype "passive"))
      (node (ref "R723") (pin "2") (pinfunction "2_2") (pintype "passive"))
      (node (ref "U101") (pin "33") (pinfunction "PD7_33") (pintype "bidirectional"))
    )
    (net (code "112") (name "USB_ID") (class "Default")
      (node (ref "R725") (pin "2") (pinfunction "2_2") (pintype "passive"))
      (node (ref "U101") (pin "7") (pinfunction "PB1_7") (pintype "bidirectional"))
    )
    (net (code "113") (name "USB_RESET") (class "Default")
      (node (ref "R151") (pin "2") (pinfunction "2_2") (pintype "passive"))
      (node (ref "R721") (pin "2") (pinfunction "2_2") (pintype "passive"))
    )
    (net (code "114") (name "USB_RESET_DRV") (class "Default")
      (node (ref "R151") (pin "1") (pinfunction "1_1") (pintype "passive"))
      (node (ref "U101") (pin "31") (pinfunction "PD5_31") (pintype "bidirectional"))
    )
    (net (code "115") (name "VBAT") (class "Default")
      (node (ref "C201") (pin "1") (pinfunction "1_1") (pintype "passive"))
      (node (ref "C901") (pin "1") (pinfunction "1_1") (pintype "passive"))
      (node (ref "D1122") (pin "A") (pinfunction "A_A") (pintype "passive"))
      (node (ref "D201") (pin "C") (pinfunction "C_C") (pintype "passive"))
      (node (ref "R1132") (pin "1") (pinfunction "1_1") (pintype "passive"))
      (node (ref "RPOLY901") (pin "2") (pinfunction "2_2") (pintype "passive"))
      (node (ref "U201") (pin "P$4") (pinfunction "VBAT_P$4") (pintype "power_in"))
      (node (ref "U201") (pin "P$5") (pinfunction "VBAT_P$5") (pintype "power_in"))
      (node (ref "U201") (pin "P$6") (pinfunction "VBAT_P$6") (pintype "power_in"))
    )
    (net (code "116") (name "VREF") (class "Default")
      (node (ref "JP111") (pin "4") (pinfunction "4_4") (pintype "passive"))
      (node (ref "R111") (pin "1") (pinfunction "1_1") (pintype "passive"))
    )
    (net (code "117") (name "XO_AMP") (class "Default")
      (node (ref "R1013") (pin "1") (pinfunction "1_1") (pintype "passive"))
      (node (ref "U1011") (pin "1") (pinfunction "OUT_1") (pintype "output"))
    )
    (net (code "118") (name "XO_DRV") (class "Default")
      (node (ref "U1001") (pin "3") (pinfunction "OUT_3") (pintype "output"))
      (node (ref "U1011") (pin "3") (pinfunction "+IN_3") (pintype "input"))
    )
    (net (code "119") (name "XO_LP") (class "Default")
      (node (ref "C1001") (pin "1") (pinfunction "1_1") (pintype "passive"))
      (node (ref "R1001") (pin "2") (pinfunction "2_2") (pintype "passive"))
      (node (ref "R1002") (pin "1") (pinfunction "1_1") (pintype "passive"))
      (node (ref "U1021") (pin "3") (pinfunction "+IN_3") (pintype "input"))
    )
    (net (code "120") (name "XO_VC") (class "Default")
      (node (ref "R1002") (pin "2") (pinfunction "2_2") (pintype "passive"))
      (node (ref "U1001") (pin "1") (pinfunction "VC_1") (pintype "input"))
    )
    (net (code "121") (name "XO_VC_PWM") (class "Default")
      (node (ref "R1001") (pin "1") (pinfunction "1_1") (pintype "passive"))
      (node (ref "U101") (pin "18") (pinfunction "PC2_18") (pintype "bidirectional"))
    )
    (net (code "122") (name "unconnected-(J801-PadS4)") (class "Default")
      (node (ref "J801") (pin "S4") (pinfunction "S4_S4") (pintype "passive"))
    )
    (net (code "123") (name "unconnected-(J801-PadS8)") (class "Default")
      (node (ref "J801") (pin "S8") (pinfunction "S8_S8") (pintype "passive"))
    )
    (net (code "124") (name "unconnected-(J801-PadSW)") (class "Default")
      (node (ref "J801") (pin "SW") (pinfunction "SW_SW") (pintype "passive"))
    )
    (net (code "125") (name "unconnected-(J801-PadT1)") (class "Default")
      (node (ref "J801") (pin "T1") (pinfunction "T1_T1") (pintype "bidirectional"))
    )
    (net (code "126") (name "unconnected-(J801-PadT2)") (class "Default")
      (node (ref "J801") (pin "T2") (pinfunction "T2_T2") (pintype "bidirectional"))
    )
    (net (code "127") (name "unconnected-(J801-PadT3)") (class "Default")
      (node (ref "J801") (pin "T3") (pinfunction "T3_T3") (pintype "bidirectional"))
    )
    (net (code "128") (name "unconnected-(J801-PadT5)") (class "Default")
      (node (ref "J801") (pin "T5") (pinfunction "T5_T5") (pintype "input"))
    )
    (net (code "129") (name "unconnected-(J801-PadT7)") (class "Default")
      (node (ref "J801") (pin "T7") (pinfunction "T7_T7") (pintype "bidirectional"))
    )
    (net (code "130") (name "unconnected-(J801-PadT8)") (class "Default")
      (node (ref "J801") (pin "T8") (pinfunction "T8_T8") (pintype "bidirectional"))
    )
    (net (code "131") (name "unconnected-(J901-Pad2)") (class "Default")
      (node (ref "J901") (pin "2") (pinfunction "2_2") (pintype "passive"))
    )
    (net (code "132") (name "unconnected-(JP111-Pad8)") (class "Default")
      (node (ref "JP111") (pin "8") (pinfunction "8_8") (pintype "passive"))
    )
    (net (code "133") (name "unconnected-(JP131-Pad3)") (class "Default")
      (node (ref "JP131") (pin "3") (pinfunction "3_3") (pintype "passive"))
    )
    (net (code "134") (name "unconnected-(JP131-Pad4)") (class "Default")
      (node (ref "JP131") (pin "4") (pinfunction "4_4") (pintype "passive"))
    )
    (net (code "135") (name "unconnected-(U201-ADC1-PadP$23)") (class "Default")
      (node (ref "U201") (pin "P$23") (pinfunction "ADC1_P$23") (pintype "input"))
    )
    (net (code "136") (name "unconnected-(U201-ADC2-PadP$24)") (class "Default")
      (node (ref "U201") (pin "P$24") (pinfunction "ADC2_P$24") (pintype "input"))
    )
    (net (code "137") (name "unconnected-(U201-COL0-PadP$62)") (class "Default")
      (node (ref "U201") (pin "P$62") (pinfunction "COL0_P$62") (pintype "input"))
    )
    (net (code "138") (name "unconnected-(U201-COL1-PadP$61)") (class "Default")
      (node (ref "U201") (pin "P$61") (pinfunction "COL1_P$61") (pintype "input"))
    )
    (net (code "139") (name "unconnected-(U201-COL2-PadP$60)") (class "Default")
      (node (ref "U201") (pin "P$60") (pinfunction "COL2_P$60") (pintype "input"))
    )
    (net (code "140") (name "unconnected-(U201-COL3-PadP$59)") (class "Default")
      (node (ref "U201") (pin "P$59") (pinfunction "COL3_P$59") (pintype "input"))
    )
    (net (code "141") (name "unconnected-(U201-GPIO5-PadP$43)") (class "Default")
      (node (ref "U201") (pin "P$43") (pinfunction "GPIO5_P$43") (pintype "bidirectional"))
    )
    (net (code "142") (name "unconnected-(U201-GPIO6-PadP$44)") (class "Default")
      (node (ref "U201") (pin "P$44") (pinfunction "GPIO6_P$44") (pintype "bidirectional"))
    )
    (net (code "143") (name "unconnected-(U201-MIC1N-PadP$20)") (class "Default")
      (node (ref "U201") (pin "P$20") (pinfunction "MIC1N_P$20") (pintype "input"))
    )
    (net (code "144") (name "unconnected-(U201-MIC1P-PadP$19)") (class "Default")
      (node (ref "U201") (pin "P$19") (pinfunction "MIC1P_P$19") (pintype "input"))
    )
    (net (code "145") (name "unconnected-(U201-PWM1-PadP$42)") (class "Default")
      (node (ref "U201") (pin "P$42") (pinfunction "PWM1_P$42") (pintype "output"))
    )
    (net (code "146") (name "unconnected-(U201-PWM2-PadP$41)") (class "Default")
      (node (ref "U201") (pin "P$41") (pinfunction "PWM2_P$41") (pintype "output"))
    )
    (net (code "147") (name "unconnected-(U201-ROW0-PadP$58)") (class "Default")
      (node (ref "U201") (pin "P$58") (pinfunction "ROW0_P$58") (pintype "output"))
    )
    (net (code "148") (name "unconnected-(U201-ROW1-PadP$57)") (class "Default")
      (node (ref "U201") (pin "P$57") (pinfunction "ROW1_P$57") (pintype "output"))
    )
    (net (code "149") (name "unconnected-(U201-ROW2-PadP$56)") (class "Default")
      (node (ref "U201") (pin "P$56") (pinfunction "ROW2_P$56") (pintype "output"))
    )
    (net (code "150") (name "unconnected-(U201-ROW3-PadP$55)") (class "Default")
      (node (ref "U201") (pin "P$55") (pinfunction "ROW3_P$55") (pintype "output"))
    )
    (net (code "151") (name "unconnected-(U201-SPK1N-PadP$22)") (class "Default")
      (node (ref "U201") (pin "P$22") (pinfunction "SPK1N_P$22") (pintype "output"))
    )
    (net (code "152") (name "unconnected-(U201-SPK1P-PadP$21)") (class "Default")
      (node (ref "U201") (pin "P$21") (pinfunction "SPK1P_P$21") (pintype "output"))
    )
    (net (code "153") (name "unconnected-(U201-USB_DM-PadP$27)") (class "Default")
      (node (ref "U201") (pin "P$27") (pinfunction "USB_DM_P$27") (pintype "bidirectional"))
    )
    (net (code "154") (name "unconnected-(U201-USB_DP-PadP$26)") (class "Default")
      (node (ref "U201") (pin "P$26") (pinfunction "USB_DP_P$26") (pintype "bidirectional"))
    )
    (net (code "155") (name "unconnected-(U301-AUX_CL-Pad7)") (class "Default")
      (node (ref "U301") (pin "7") (pinfunction "AUX_CL_7") (pintype "output"))
    )
    (net (code "156") (name "unconnected-(U301-AUX_DA-Pad21)") (class "Default")
      (node (ref "U301") (pin "21") (pinfunction "AUX_DA_21") (pintype "bidirectional"))
    )
    (net (code "157") (name "unconnected-(U401-NC-Pad5)") (class "Default")
      (node (ref "U401") (pin "5") (pinfunction "NC_5") (pintype "no_connect"))
    )
    (net (code "158") (name "unconnected-(U401-SDO-Pad6)") (class "Default")
      (node (ref "U401") (pin "6") (pinfunction "SDO_6") (pintype "output"))
    )
    (net (code "159") (name "unconnected-(U501-ALERT-Pad3)") (class "Default")
      (node (ref "U501") (pin "3") (pinfunction "ALERT_3") (pintype "output"))
    )
    (net (code "160") (name "unconnected-(U601-FILT-Pad6)") (class "Default")
      (node (ref "U601") (pin "6") (pinfunction "FILT_6") (pintype "passive"))
    )
    (net (code "161") (name "unconnected-(U601-SYSCLK-Pad9)") (class "Default")
      (node (ref "U601") (pin "9") (pinfunction "SYSCLK_9") (pintype "bidirectional"))
    )
    (net (code "162") (name "unconnected-(U601-TCXO_EN-Pad15)") (class "Default")
      (node (ref "U601") (pin "15") (pinfunction "TCXO_EN_15") (pintype "bidirectional"))
    )
    (net (code "163") (name "unconnected-(U1121-REF-Pad1)") (class "Default")
      (node (ref "U1121") (pin "1") (pinfunction "REF_1") (pintype "no_connect"))
    )
  )
)
